# electrosteel2020_10_arrange6_synthboards.net
KiCad netlist of a schematic drawn in EAGLE
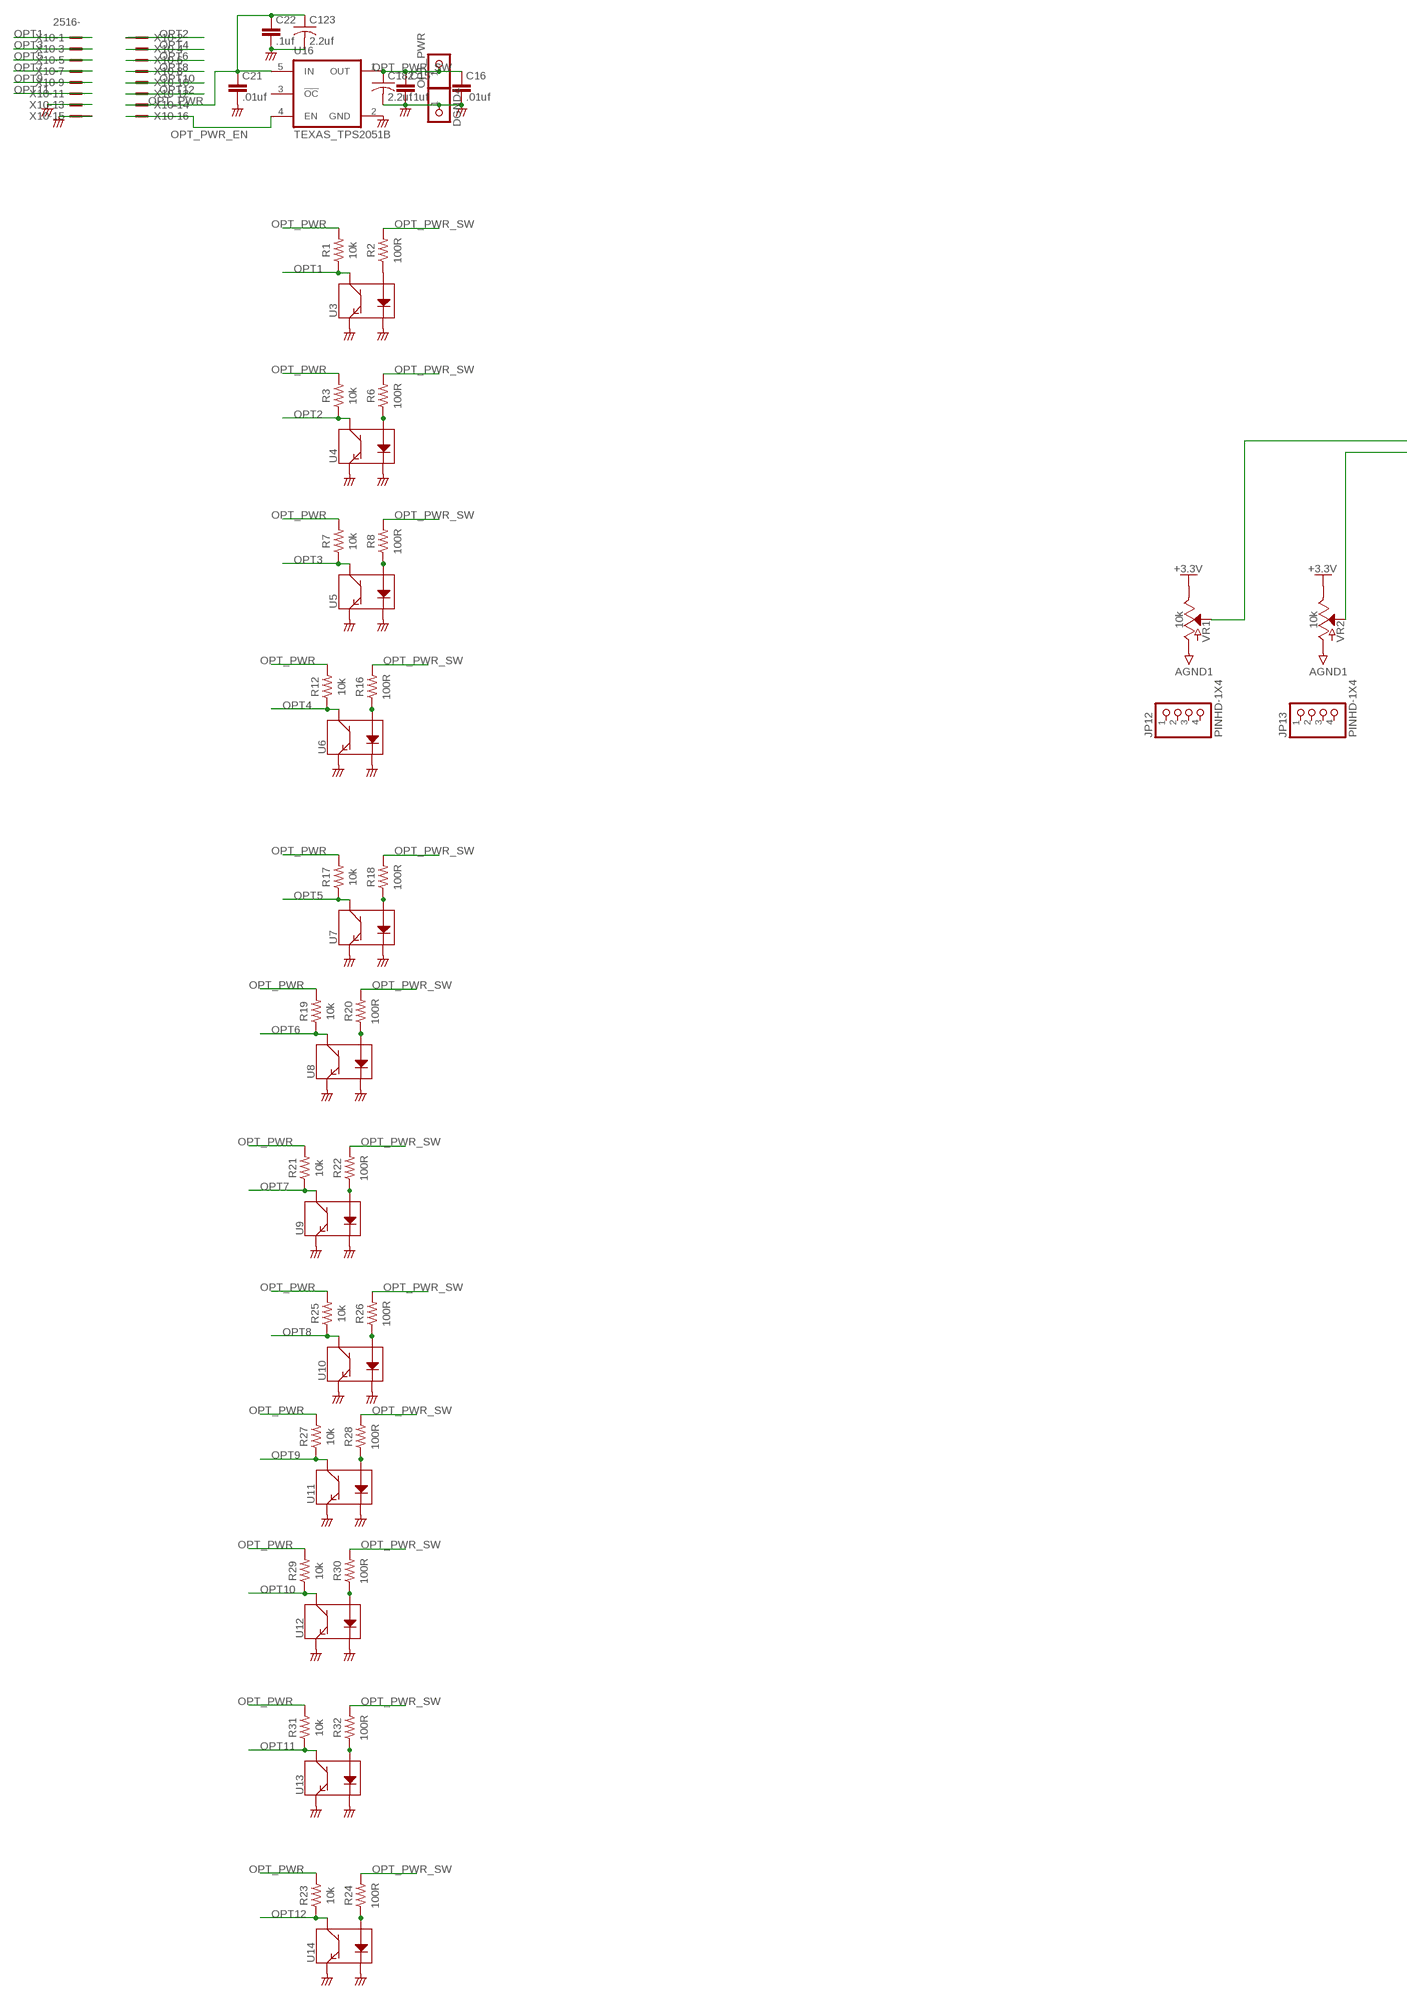
[diagram p0: schematic, sheet 1, part 1 of 3]
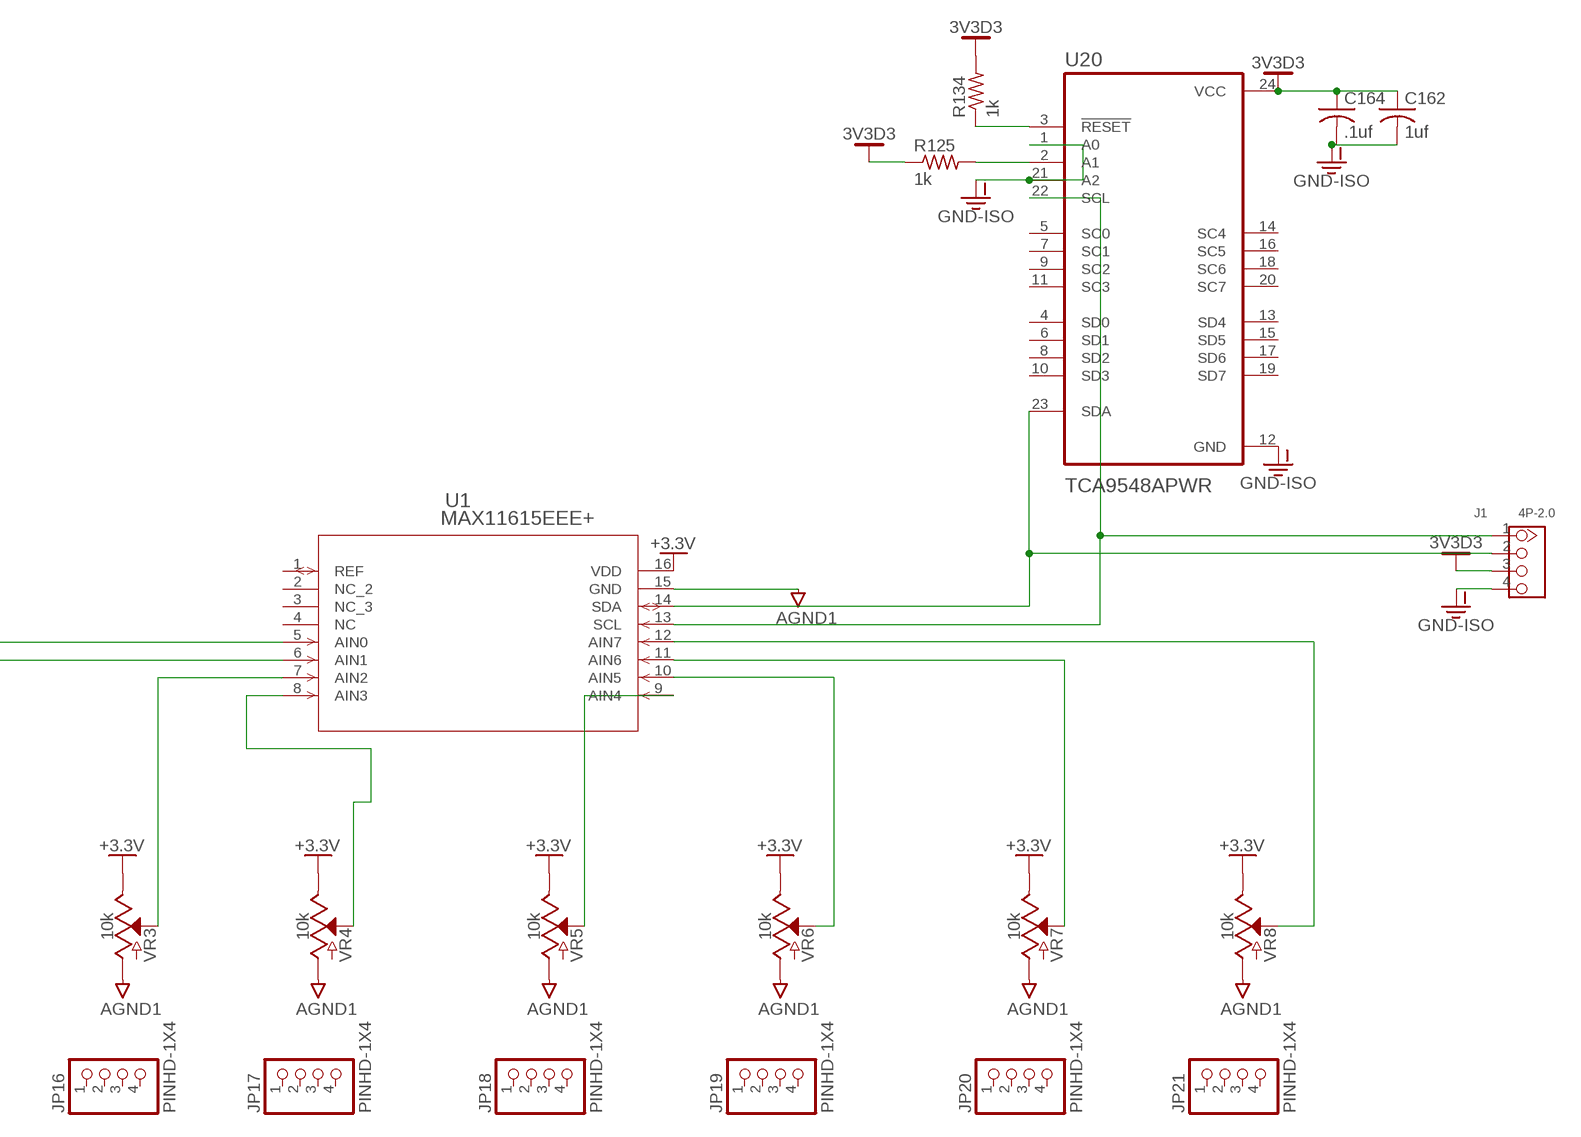
[diagram p1: schematic, sheet 1, part 2 of 3]
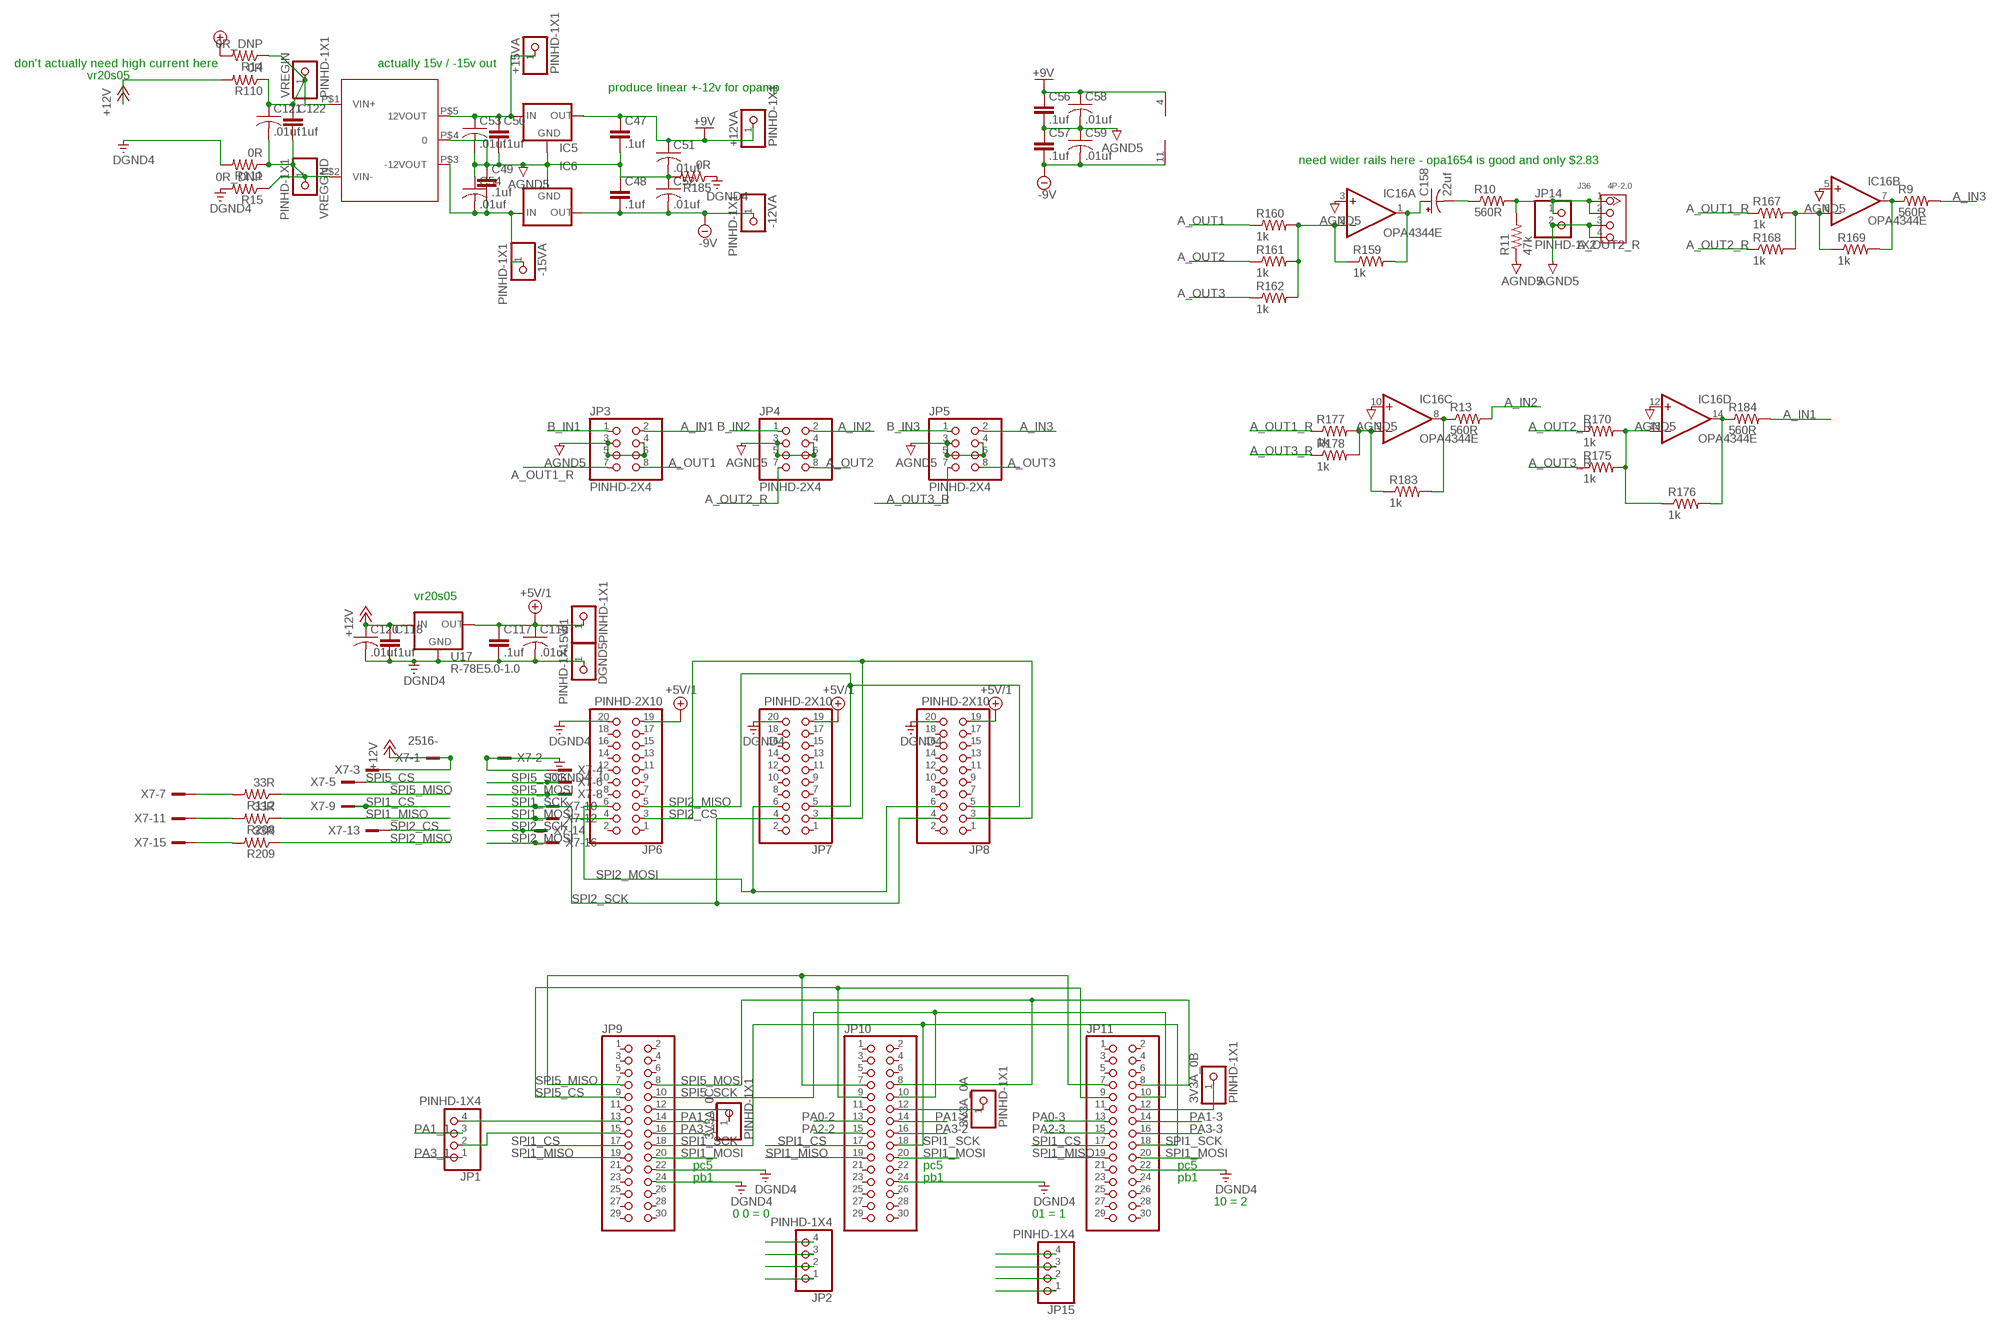
[diagram p2: schematic, sheet 1, part 3 of 3]

(export (version "E")
  (design (tool "Eeschema 10.0.6"))
  (components
    (comp (ref "+12VA")
      (value "PINHD-1X1")
      (footprint "eagle-import:1X01")
      (fields (field (name "PARTNO") "*DNP"))
      (libsource (lib "eagle-import") (part "PINHD-1X1"))
    )
    (comp (ref "+15VA")
      (value "PINHD-1X1")
      (footprint "eagle-import:1X01")
      (fields (field (name "PARTNO") "*DNP"))
      (libsource (lib "eagle-import") (part "PINHD-1X1"))
    )
    (comp (ref "-12VA")
      (value "PINHD-1X1")
      (footprint "eagle-import:1X01")
      (fields (field (name "PARTNO") "*DNP"))
      (libsource (lib "eagle-import") (part "PINHD-1X1"))
    )
    (comp (ref "-15VA")
      (value "PINHD-1X1")
      (footprint "eagle-import:1X01")
      (fields (field (name "PARTNO") "*DNP"))
      (libsource (lib "eagle-import") (part "PINHD-1X1"))
    )
    (comp (ref "3V3A_0A")
      (value "PINHD-1X1")
      (footprint "eagle-import:1X01")
      (fields (field (name "PARTNO") "*DNP"))
      (libsource (lib "eagle-import") (part "PINHD-1X1"))
    )
    (comp (ref "3V3A_0B")
      (value "PINHD-1X1")
      (footprint "eagle-import:1X01")
      (fields (field (name "PARTNO") "*DNP"))
      (libsource (lib "eagle-import") (part "PINHD-1X1"))
    )
    (comp (ref "3V3A_0C")
      (value "PINHD-1X1")
      (footprint "eagle-import:1X01")
      (fields (field (name "PARTNO") "*DNP"))
      (libsource (lib "eagle-import") (part "PINHD-1X1"))
    )
    (comp (ref "5V/1")
      (value "PINHD-1X1")
      (footprint "eagle-import:1X01")
      (fields (field (name "PARTNO") "*DNP"))
      (libsource (lib "eagle-import") (part "PINHD-1X1"))
    )
    (comp (ref "C15")
      (value ".1uf")
      (footprint "eagle-import:0402")
      (fields (field (name "PARTNO") "CC0402KRX7R8BB104"))
      (libsource (lib "eagle-import") (part "CAP_0402"))
    )
    (comp (ref "C16")
      (value ".01uf")
      (footprint "eagle-import:0402")
      (fields (field (name "PARTNO") "CC0402KRX7R8BB103"))
      (libsource (lib "eagle-import") (part "CAP_0402"))
    )
    (comp (ref "C21")
      (value ".01uf")
      (footprint "eagle-import:0402")
      (fields (field (name "PARTNO") "CC0402KRX7R8BB103"))
      (libsource (lib "eagle-import") (part "CAP_0402"))
    )
    (comp (ref "C22")
      (value ".1uf")
      (footprint "eagle-import:0402")
      (fields (field (name "PARTNO") "CC0402KRX7R8BB104"))
      (libsource (lib "eagle-import") (part "CAP_0402"))
    )
    (comp (ref "C47")
      (value ".1uf")
      (footprint "eagle-import:0402")
      (fields (field (name "PARTNO") "CC0402KRX7R8BB104"))
      (libsource (lib "eagle-import") (part "CAP_0402"))
    )
    (comp (ref "C48")
      (value ".1uf")
      (footprint "eagle-import:0402")
      (fields (field (name "PARTNO") "CC0402KRX7R8BB104"))
      (libsource (lib "eagle-import") (part "CAP_0402"))
    )
    (comp (ref "C49")
      (value ".1uf")
      (footprint "eagle-import:0402")
      (fields (field (name "PARTNO") "CC0402KRX7R8BB104"))
      (libsource (lib "eagle-import") (part "CAP_0402"))
    )
    (comp (ref "C50")
      (value ".1uf")
      (footprint "eagle-import:0402")
      (fields (field (name "PARTNO") "CC0402KRX7R8BB104"))
      (libsource (lib "eagle-import") (part "CAP_0402"))
    )
    (comp (ref "C51")
      (value ".01uf")
      (footprint "eagle-import:C0201")
      (fields (field (name "PARTNO") "TMK063B7103KP-F"))
      (libsource (lib "eagle-import") (part "C-USC0201"))
    )
    (comp (ref "C52")
      (value ".01uf")
      (footprint "eagle-import:C0201")
      (fields (field (name "PARTNO") "TMK063B7103KP-F"))
      (libsource (lib "eagle-import") (part "C-USC0201"))
    )
    (comp (ref "C53")
      (value ".01uf")
      (footprint "eagle-import:C0201")
      (fields (field (name "PARTNO") "TMK063B7103KP-F"))
      (libsource (lib "eagle-import") (part "C-USC0201"))
    )
    (comp (ref "C54")
      (value ".01uf")
      (footprint "eagle-import:C0201")
      (fields (field (name "PARTNO") "TMK063B7103KP-F"))
      (libsource (lib "eagle-import") (part "C-USC0201"))
    )
    (comp (ref "C56")
      (value ".1uf")
      (footprint "eagle-import:0402")
      (fields (field (name "PARTNO") "CC0402KRX7R8BB104"))
      (libsource (lib "eagle-import") (part "CAP_0402"))
    )
    (comp (ref "C57")
      (value ".1uf")
      (footprint "eagle-import:0402")
      (fields (field (name "PARTNO") "CC0402KRX7R8BB104"))
      (libsource (lib "eagle-import") (part "CAP_0402"))
    )
    (comp (ref "C58")
      (value ".01uf")
      (footprint "eagle-import:C0201")
      (fields (field (name "PARTNO") "TMK063B7103KP-F"))
      (libsource (lib "eagle-import") (part "C-USC0201"))
    )
    (comp (ref "C59")
      (value ".01uf")
      (footprint "eagle-import:C0201")
      (fields (field (name "PARTNO") "TMK063B7103KP-F"))
      (libsource (lib "eagle-import") (part "C-USC0201"))
    )
    (comp (ref "C117")
      (value ".1uf")
      (footprint "eagle-import:0402")
      (fields (field (name "PARTNO") "CC0402KRX7R8BB104"))
      (libsource (lib "eagle-import") (part "CAP_0402"))
    )
    (comp (ref "C118")
      (value ".1uf")
      (footprint "eagle-import:0402")
      (fields (field (name "PARTNO") "CC0402KRX7R8BB104"))
      (libsource (lib "eagle-import") (part "CAP_0402"))
    )
    (comp (ref "C119")
      (value ".01uf")
      (footprint "eagle-import:C0201")
      (fields (field (name "PARTNO") "TMK063B7103KP-F"))
      (libsource (lib "eagle-import") (part "C-USC0201"))
    )
    (comp (ref "C120")
      (value ".01uf")
      (footprint "eagle-import:C0201")
      (fields (field (name "PARTNO") "TMK063B7103KP-F"))
      (libsource (lib "eagle-import") (part "C-USC0201"))
    )
    (comp (ref "C121")
      (value ".01uf")
      (footprint "eagle-import:C0201")
      (fields (field (name "PARTNO") "TMK063B7103KP-F"))
      (libsource (lib "eagle-import") (part "C-USC0201"))
    )
    (comp (ref "C122")
      (value ".1uf")
      (footprint "eagle-import:0402")
      (fields (field (name "PARTNO") "CC0402KRX7R8BB104"))
      (libsource (lib "eagle-import") (part "CAP_0402"))
    )
    (comp (ref "C123")
      (value "2.2uf")
      (footprint "eagle-import:C1206")
      (fields (field (name "PARTNO") "T491A225K020AT"))
      (libsource (lib "eagle-import") (part "C-USC1206"))
    )
    (comp (ref "C158")
      (value "22uf")
      (footprint "eagle-import:PANASONIC_D")
      (fields (field (name "PARTNO") "EEE-1CA220NP"))
      (libsource (lib "eagle-import") (part "CPOL-USD"))
    )
    (comp (ref "C162")
      (value "1uf")
      (footprint "eagle-import:C1206K")
      (fields (field (name "PARTNO") "C3216X7R1E105K085AA"))
      (libsource (lib "eagle-import") (part "C-USC1206K"))
    )
    (comp (ref "C164")
      (value ".1uf")
      (footprint "eagle-import:C0603K")
      (fields (field (name "PARTNO") "CC0603KRX7R8BB104"))
      (libsource (lib "eagle-import") (part "C-USC0603K"))
    )
    (comp (ref "C182")
      (value "2.2uf")
      (footprint "eagle-import:C1206")
      (fields (field (name "PARTNO") "T491A225K020AT"))
      (libsource (lib "eagle-import") (part "C-USC1206"))
    )
    (comp (ref "DGND4")
      (value "PINHD-1X1")
      (footprint "eagle-import:1X01")
      (fields (field (name "PARTNO") "*DNP"))
      (libsource (lib "eagle-import") (part "adafruit_PINHD-1X1"))
    )
    (comp (ref "DGND5")
      (value "PINHD-1X1")
      (footprint "eagle-import:1X01")
      (fields (field (name "PARTNO") "*DNP"))
      (libsource (lib "eagle-import") (part "PINHD-1X1"))
    )
    (comp (ref "IC5")
      (value "78LXX")
      (footprint "eagle-import:78LXX")
      (fields (field (name "PARTNO") "LM78L12ACZ/LFT7"))
      (libsource (lib "eagle-import") (part "78LXX"))
    )
    (comp (ref "IC6")
      (value "79LXX")
      (footprint "eagle-import:79LXX")
      (fields (field (name "PARTNO") "L79L12ACZ-TR"))
      (libsource (lib "eagle-import") (part "79LXX"))
    )
    (comp (ref "IC16")
      (value "OPA4344E")
      (footprint "eagle-import:TSSOP14")
      (fields (field (name "PARTNO") "OPA1654AIPWR"))
      (libsource (lib "eagle-import") (part "OPA4E344"))
    )
    (comp (ref "J1")
      (value "4P-2.0")
      (footprint "eagle-import:HW4-2.0")
      (fields (field (name "PARTNO") "110990030"))
      (libsource (lib "eagle-import") (part "GROVE-CONNECTOR-DIP(4P-2.0)"))
    )
    (comp (ref "J36")
      (value "4P-2.0")
      (footprint "eagle-import:HW4-2.0")
      (fields (field (name "PARTNO") "110990030"))
      (libsource (lib "eagle-import") (part "GROVE-CONNECTOR-DIP(4P-2.0)"))
    )
    (comp (ref "JP1")
      (value "PINHD-1X4")
      (footprint "eagle-import:1X04")
      (libsource (lib "eagle-import") (part "PINHD-1X4"))
    )
    (comp (ref "JP2")
      (value "PINHD-1X4")
      (footprint "eagle-import:1X04")
      (libsource (lib "eagle-import") (part "PINHD-1X4"))
    )
    (comp (ref "JP3")
      (value "PINHD-2X4")
      (footprint "eagle-import:2X04")
      (fields (field (name "PARTNO") "77313-101-08LF"))
      (libsource (lib "eagle-import") (part "PINHD-2X4"))
    )
    (comp (ref "JP4")
      (value "PINHD-2X4")
      (footprint "eagle-import:2X04")
      (fields (field (name "PARTNO") "77313-101-08LF"))
      (libsource (lib "eagle-import") (part "PINHD-2X4"))
    )
    (comp (ref "JP5")
      (value "PINHD-2X4")
      (footprint "eagle-import:2X04")
      (fields (field (name "PARTNO") "77313-101-08LF"))
      (libsource (lib "eagle-import") (part "PINHD-2X4"))
    )
    (comp (ref "JP6")
      (value "PINHD-2X10")
      (footprint "eagle-import:2X10")
      (fields (field (name "PARTNO") "77313-101-20LF"))
      (libsource (lib "eagle-import") (part "PINHD-2X10"))
    )
    (comp (ref "JP7")
      (value "PINHD-2X10")
      (footprint "eagle-import:2X10")
      (fields (field (name "PARTNO") "77313-101-20LF"))
      (libsource (lib "eagle-import") (part "PINHD-2X10"))
    )
    (comp (ref "JP8")
      (value "PINHD-2X10")
      (footprint "eagle-import:2X10")
      (fields (field (name "PARTNO") "77313-101-20LF"))
      (libsource (lib "eagle-import") (part "PINHD-2X10"))
    )
    (comp (ref "JP9")
      (value "PINHD-2X15")
      (footprint "eagle-import:2X15")
      (fields (field (name "PARTNO") "77313-101-30LF"))
      (libsource (lib "eagle-import") (part "PINHD-2X15"))
    )
    (comp (ref "JP10")
      (value "PINHD-2X15")
      (footprint "eagle-import:2X15")
      (fields (field (name "PARTNO") "77313-101-30LF"))
      (libsource (lib "eagle-import") (part "PINHD-2X15"))
    )
    (comp (ref "JP11")
      (value "PINHD-2X15")
      (footprint "eagle-import:2X15")
      (fields (field (name "PARTNO") "77313-101-30LF"))
      (libsource (lib "eagle-import") (part "PINHD-2X15"))
    )
    (comp (ref "JP12")
      (value "PINHD-1X4")
      (footprint "eagle-import:1X04")
      (libsource (lib "eagle-import") (part "PINHD-1X4"))
    )
    (comp (ref "JP13")
      (value "PINHD-1X4")
      (footprint "eagle-import:1X04")
      (libsource (lib "eagle-import") (part "PINHD-1X4"))
    )
    (comp (ref "JP14")
      (value "PINHD-1X2")
      (footprint "eagle-import:1X02")
      (fields (field (name "PARTNO") "*DNP"))
      (libsource (lib "eagle-import") (part "PINHD-1X2"))
    )
    (comp (ref "JP15")
      (value "PINHD-1X4")
      (footprint "eagle-import:1X04")
      (libsource (lib "eagle-import") (part "PINHD-1X4"))
    )
    (comp (ref "JP16")
      (value "PINHD-1X4")
      (footprint "eagle-import:1X04")
      (libsource (lib "eagle-import") (part "PINHD-1X4"))
    )
    (comp (ref "JP17")
      (value "PINHD-1X4")
      (footprint "eagle-import:1X04")
      (libsource (lib "eagle-import") (part "PINHD-1X4"))
    )
    (comp (ref "JP18")
      (value "PINHD-1X4")
      (footprint "eagle-import:1X04")
      (libsource (lib "eagle-import") (part "PINHD-1X4"))
    )
    (comp (ref "JP19")
      (value "PINHD-1X4")
      (footprint "eagle-import:1X04")
      (libsource (lib "eagle-import") (part "PINHD-1X4"))
    )
    (comp (ref "JP20")
      (value "PINHD-1X4")
      (footprint "eagle-import:1X04")
      (libsource (lib "eagle-import") (part "PINHD-1X4"))
    )
    (comp (ref "JP21")
      (value "PINHD-1X4")
      (footprint "eagle-import:1X04")
      (libsource (lib "eagle-import") (part "PINHD-1X4"))
    )
    (comp (ref "OPT_PWR")
      (value "PINHD-1X1")
      (footprint "eagle-import:1X01")
      (fields (field (name "PARTNO") "*DNP"))
      (libsource (lib "eagle-import") (part "adafruit_PINHD-1X1"))
    )
    (comp (ref "R1")
      (value "10k")
      (footprint "eagle-import:RESC1608X60")
      (fields (field (name "PARTNO") "ESR03EZPF1002"))
      (libsource (lib "eagle-import") (part "R-USCHIP-0603(1608-METRIC)_"))
    )
    (comp (ref "R2")
      (value "100R")
      (footprint "eagle-import:RESC1608X60")
      (fields (field (name "PARTNO") "ESR03EZPJ101"))
      (libsource (lib "eagle-import") (part "R-USCHIP-0603(1608-METRIC)_"))
    )
    (comp (ref "R3")
      (value "10k")
      (footprint "eagle-import:RESC1608X60")
      (fields (field (name "PARTNO") "ESR03EZPF1002"))
      (libsource (lib "eagle-import") (part "R-USCHIP-0603(1608-METRIC)_"))
    )
    (comp (ref "R6")
      (value "100R")
      (footprint "eagle-import:RESC1608X60")
      (fields (field (name "PARTNO") "ESR03EZPJ101"))
      (libsource (lib "eagle-import") (part "R-USCHIP-0603(1608-METRIC)_"))
    )
    (comp (ref "R7")
      (value "10k")
      (footprint "eagle-import:RESC1608X60")
      (fields (field (name "PARTNO") "ESR03EZPF1002"))
      (libsource (lib "eagle-import") (part "R-USCHIP-0603(1608-METRIC)_"))
    )
    (comp (ref "R8")
      (value "100R")
      (footprint "eagle-import:RESC1608X60")
      (fields (field (name "PARTNO") "ESR03EZPJ101"))
      (libsource (lib "eagle-import") (part "R-USCHIP-0603(1608-METRIC)_"))
    )
    (comp (ref "R9")
      (value "560R")
      (footprint "eagle-import:R0603")
      (fields (field (name "PARTNO") "ESR03EZPF5600"))
      (libsource (lib "eagle-import") (part "R-US_R0603"))
    )
    (comp (ref "R10")
      (value "560R")
      (footprint "eagle-import:R0603")
      (fields (field (name "PARTNO") "ESR03EZPF5600"))
      (libsource (lib "eagle-import") (part "R-US_R0603"))
    )
    (comp (ref "R11")
      (value "47k")
      (footprint "eagle-import:R0603")
      (fields (field (name "PARTNO") "ESR03EZPJ473"))
      (libsource (lib "eagle-import") (part "R-US_R0603"))
    )
    (comp (ref "R12")
      (value "10k")
      (footprint "eagle-import:RESC1608X60")
      (fields (field (name "PARTNO") "ESR03EZPF1002"))
      (libsource (lib "eagle-import") (part "R-USCHIP-0603(1608-METRIC)_"))
    )
    (comp (ref "R13")
      (value "560R")
      (footprint "eagle-import:R0603")
      (fields (field (name "PARTNO") "ESR03EZPF5600"))
      (libsource (lib "eagle-import") (part "R-US_R0603"))
    )
    (comp (ref "R14")
      (value "0R_DNP")
      (footprint "eagle-import:R0603")
      (fields (field (name "PARTNO") "*DNP"))
      (libsource (lib "eagle-import") (part "R-US_R0603"))
    )
    (comp (ref "R15")
      (value "0R_DNP")
      (footprint "eagle-import:R0603")
      (fields (field (name "PARTNO") "*DNP"))
      (libsource (lib "eagle-import") (part "R-US_R0603"))
    )
    (comp (ref "R16")
      (value "100R")
      (footprint "eagle-import:RESC1608X60")
      (fields (field (name "PARTNO") "ESR03EZPJ101"))
      (libsource (lib "eagle-import") (part "R-USCHIP-0603(1608-METRIC)_"))
    )
    (comp (ref "R17")
      (value "10k")
      (footprint "eagle-import:RESC1608X60")
      (fields (field (name "PARTNO") "ESR03EZPF1002"))
      (libsource (lib "eagle-import") (part "R-USCHIP-0603(1608-METRIC)_"))
    )
    (comp (ref "R18")
      (value "100R")
      (footprint "eagle-import:RESC1608X60")
      (fields (field (name "PARTNO") "ESR03EZPJ101"))
      (libsource (lib "eagle-import") (part "R-USCHIP-0603(1608-METRIC)_"))
    )
    (comp (ref "R19")
      (value "10k")
      (footprint "eagle-import:RESC1608X60")
      (fields (field (name "PARTNO") "ESR03EZPF1002"))
      (libsource (lib "eagle-import") (part "R-USCHIP-0603(1608-METRIC)_"))
    )
    (comp (ref "R20")
      (value "100R")
      (footprint "eagle-import:RESC1608X60")
      (fields (field (name "PARTNO") "ESR03EZPJ101"))
      (libsource (lib "eagle-import") (part "R-USCHIP-0603(1608-METRIC)_"))
    )
    (comp (ref "R21")
      (value "10k")
      (footprint "eagle-import:RESC1608X60")
      (fields (field (name "PARTNO") "ESR03EZPF1002"))
      (libsource (lib "eagle-import") (part "R-USCHIP-0603(1608-METRIC)_"))
    )
    (comp (ref "R22")
      (value "100R")
      (footprint "eagle-import:RESC1608X60")
      (fields (field (name "PARTNO") "ESR03EZPJ101"))
      (libsource (lib "eagle-import") (part "R-USCHIP-0603(1608-METRIC)_"))
    )
    (comp (ref "R23")
      (value "10k")
      (footprint "eagle-import:RESC1608X60")
      (fields (field (name "PARTNO") "ESR03EZPF1002"))
      (libsource (lib "eagle-import") (part "R-USCHIP-0603(1608-METRIC)_"))
    )
    (comp (ref "R24")
      (value "100R")
      (footprint "eagle-import:RESC1608X60")
      (fields (field (name "PARTNO") "ESR03EZPJ101"))
      (libsource (lib "eagle-import") (part "R-USCHIP-0603(1608-METRIC)_"))
    )
    (comp (ref "R25")
      (value "10k")
      (footprint "eagle-import:RESC1608X60")
      (fields (field (name "PARTNO") "ESR03EZPF1002"))
      (libsource (lib "eagle-import") (part "R-USCHIP-0603(1608-METRIC)_"))
    )
    (comp (ref "R26")
      (value "100R")
      (footprint "eagle-import:RESC1608X60")
      (fields (field (name "PARTNO") "ESR03EZPJ101"))
      (libsource (lib "eagle-import") (part "R-USCHIP-0603(1608-METRIC)_"))
    )
    (comp (ref "R27")
      (value "10k")
      (footprint "eagle-import:RESC1608X60")
      (fields (field (name "PARTNO") "ESR03EZPF1002"))
      (libsource (lib "eagle-import") (part "R-USCHIP-0603(1608-METRIC)_"))
    )
    (comp (ref "R28")
      (value "100R")
      (footprint "eagle-import:RESC1608X60")
      (fields (field (name "PARTNO") "ESR03EZPJ101"))
      (libsource (lib "eagle-import") (part "R-USCHIP-0603(1608-METRIC)_"))
    )
    (comp (ref "R29")
      (value "10k")
      (footprint "eagle-import:RESC1608X60")
      (fields (field (name "PARTNO") "ESR03EZPF1002"))
      (libsource (lib "eagle-import") (part "R-USCHIP-0603(1608-METRIC)_"))
    )
    (comp (ref "R30")
      (value "100R")
      (footprint "eagle-import:RESC1608X60")
      (fields (field (name "PARTNO") "ESR03EZPJ101"))
      (libsource (lib "eagle-import") (part "R-USCHIP-0603(1608-METRIC)_"))
    )
    (comp (ref "R31")
      (value "10k")
      (footprint "eagle-import:RESC1608X60")
      (fields (field (name "PARTNO") "ESR03EZPF1002"))
      (libsource (lib "eagle-import") (part "R-USCHIP-0603(1608-METRIC)_"))
    )
    (comp (ref "R32")
      (value "100R")
      (footprint "eagle-import:RESC1608X60")
      (fields (field (name "PARTNO") "ESR03EZPJ101"))
      (libsource (lib "eagle-import") (part "R-USCHIP-0603(1608-METRIC)_"))
    )
    (comp (ref "R110")
      (value "0R")
      (footprint "eagle-import:R0603")
      (fields (field (name "PARTNO") "RCS06030000Z0EA"))
      (libsource (lib "eagle-import") (part "R-US_R0603"))
    )
    (comp (ref "R111")
      (value "0R")
      (footprint "eagle-import:R0603")
      (fields (field (name "PARTNO") "RCS06030000Z0EA"))
      (libsource (lib "eagle-import") (part "R-US_R0603"))
    )
    (comp (ref "R112")
      (value "33R")
      (footprint "eagle-import:R0201")
      (fields (field (name "PARTNO") "RC0201FR-0733RL"))
      (libsource (lib "eagle-import") (part "R-US_R0201"))
    )
    (comp (ref "R125")
      (value "1k")
      (footprint "eagle-import:R0603")
      (fields (field (name "PARTNO") "ESR03EZPF1001"))
      (libsource (lib "eagle-import") (part "R-US_R0603"))
    )
    (comp (ref "R134")
      (value "1k")
      (footprint "eagle-import:R0603")
      (fields (field (name "PARTNO") "ESR03EZPF1001"))
      (libsource (lib "eagle-import") (part "R-US_R0603"))
    )
    (comp (ref "R159")
      (value "1k")
      (footprint "eagle-import:R0603")
      (fields (field (name "PARTNO") "ESR03EZPF1001"))
      (libsource (lib "eagle-import") (part "R-US_R0603"))
    )
    (comp (ref "R160")
      (value "1k")
      (footprint "eagle-import:R0603")
      (fields (field (name "PARTNO") "ESR03EZPF1001"))
      (libsource (lib "eagle-import") (part "R-US_R0603"))
    )
    (comp (ref "R161")
      (value "1k")
      (footprint "eagle-import:R0603")
      (fields (field (name "PARTNO") "ESR03EZPF1001"))
      (libsource (lib "eagle-import") (part "R-US_R0603"))
    )
    (comp (ref "R162")
      (value "1k")
      (footprint "eagle-import:R0603")
      (fields (field (name "PARTNO") "ESR03EZPF1001"))
      (libsource (lib "eagle-import") (part "R-US_R0603"))
    )
    (comp (ref "R167")
      (value "1k")
      (footprint "eagle-import:R0603")
      (fields (field (name "PARTNO") "ESR03EZPF1001"))
      (libsource (lib "eagle-import") (part "R-US_R0603"))
    )
    (comp (ref "R168")
      (value "1k")
      (footprint "eagle-import:R0603")
      (fields (field (name "PARTNO") "ESR03EZPF1001"))
      (libsource (lib "eagle-import") (part "R-US_R0603"))
    )
    (comp (ref "R169")
      (value "1k")
      (footprint "eagle-import:R0603")
      (fields (field (name "PARTNO") "ESR03EZPF1001"))
      (libsource (lib "eagle-import") (part "R-US_R0603"))
    )
    (comp (ref "R170")
      (value "1k")
      (footprint "eagle-import:R0603")
      (fields (field (name "PARTNO") "ESR03EZPF1001"))
      (libsource (lib "eagle-import") (part "R-US_R0603"))
    )
    (comp (ref "R175")
      (value "1k")
      (footprint "eagle-import:R0603")
      (fields (field (name "PARTNO") "ESR03EZPF1001"))
      (libsource (lib "eagle-import") (part "R-US_R0603"))
    )
    (comp (ref "R176")
      (value "1k")
      (footprint "eagle-import:R0603")
      (fields (field (name "PARTNO") "ESR03EZPF1001"))
      (libsource (lib "eagle-import") (part "R-US_R0603"))
    )
    (comp (ref "R177")
      (value "1k")
      (footprint "eagle-import:R0603")
      (fields (field (name "PARTNO") "ESR03EZPF1001"))
      (libsource (lib "eagle-import") (part "R-US_R0603"))
    )
    (comp (ref "R178")
      (value "1k")
      (footprint "eagle-import:R0603")
      (fields (field (name "PARTNO") "ESR03EZPF1001"))
      (libsource (lib "eagle-import") (part "R-US_R0603"))
    )
    (comp (ref "R183")
      (value "1k")
      (footprint "eagle-import:R0603")
      (fields (field (name "PARTNO") "ESR03EZPF1001"))
      (libsource (lib "eagle-import") (part "R-US_R0603"))
    )
    (comp (ref "R184")
      (value "560R")
      (footprint "eagle-import:R0603")
      (fields (field (name "PARTNO") "ESR03EZPF5600"))
      (libsource (lib "eagle-import") (part "R-US_R0603"))
    )
    (comp (ref "R185")
      (value "0R")
      (footprint "eagle-import:R0603")
      (fields (field (name "PARTNO") "RCS06030000Z0EA"))
      (libsource (lib "eagle-import") (part "R-US_R0603"))
    )
    (comp (ref "R208")
      (value "33R")
      (footprint "eagle-import:R0201")
      (fields (field (name "PARTNO") "RC0201FR-0733RL"))
      (libsource (lib "eagle-import") (part "R-US_R0201"))
    )
    (comp (ref "R209")
      (value "33R")
      (footprint "eagle-import:R0201")
      (fields (field (name "PARTNO") "RC0201FR-0733RL"))
      (libsource (lib "eagle-import") (part "R-US_R0201"))
    )
    (comp (ref "U$3")
      (value "CMR0512S3C")
      (footprint "eagle-import:CMR0512S3C")
      (fields (field (name "PARTNO") "DPU01M-15"))
      (libsource (lib "eagle-import") (part "CMR0512S3C"))
    )
    (comp (ref "U1")
      (value "MAX11615EEE+")
      (footprint "eagle-import:21-0055H_16_MXM")
      (fields (field (name "MANUFACTURER_PART_NUMBER") "max11615eee+"))
      (libsource (lib "eagle-import") (part "MAX11615EEE+"))
    )
    (comp (ref "U3")
      (value "QRE1113")
      (footprint "eagle-import:QRE1113")
      (fields (field (name "PARTNO") "QRE1113GR"))
      (libsource (lib "eagle-import") (part "QRE1113"))
    )
    (comp (ref "U4")
      (value "QRE1113")
      (footprint "eagle-import:QRE1113")
      (fields (field (name "PARTNO") "QRE1113GR"))
      (libsource (lib "eagle-import") (part "QRE1113"))
    )
    (comp (ref "U5")
      (value "QRE1113")
      (footprint "eagle-import:QRE1113")
      (fields (field (name "PARTNO") "QRE1113GR"))
      (libsource (lib "eagle-import") (part "QRE1113"))
    )
    (comp (ref "U6")
      (value "QRE1113")
      (footprint "eagle-import:QRE1113")
      (fields (field (name "PARTNO") "QRE1113GR"))
      (libsource (lib "eagle-import") (part "QRE1113"))
    )
    (comp (ref "U7")
      (value "QRE1113")
      (footprint "eagle-import:QRE1113")
      (fields (field (name "PARTNO") "QRE1113GR"))
      (libsource (lib "eagle-import") (part "QRE1113"))
    )
    (comp (ref "U8")
      (value "QRE1113")
      (footprint "eagle-import:QRE1113")
      (fields (field (name "PARTNO") "QRE1113GR"))
      (libsource (lib "eagle-import") (part "QRE1113"))
    )
    (comp (ref "U9")
      (value "QRE1113")
      (footprint "eagle-import:QRE1113")
      (fields (field (name "PARTNO") "QRE1113GR"))
      (libsource (lib "eagle-import") (part "QRE1113"))
    )
    (comp (ref "U10")
      (value "QRE1113")
      (footprint "eagle-import:QRE1113")
      (fields (field (name "PARTNO") "QRE1113GR"))
      (libsource (lib "eagle-import") (part "QRE1113"))
    )
    (comp (ref "U11")
      (value "QRE1113")
      (footprint "eagle-import:QRE1113")
      (fields (field (name "PARTNO") "QRE1113GR"))
      (libsource (lib "eagle-import") (part "QRE1113"))
    )
    (comp (ref "U12")
      (value "QRE1113")
      (footprint "eagle-import:QRE1113")
      (fields (field (name "PARTNO") "QRE1113GR"))
      (libsource (lib "eagle-import") (part "QRE1113"))
    )
    (comp (ref "U13")
      (value "QRE1113")
      (footprint "eagle-import:QRE1113")
      (fields (field (name "PARTNO") "QRE1113GR"))
      (libsource (lib "eagle-import") (part "QRE1113"))
    )
    (comp (ref "U14")
      (value "QRE1113")
      (footprint "eagle-import:QRE1113")
      (fields (field (name "PARTNO") "QRE1113GR"))
      (libsource (lib "eagle-import") (part "QRE1113"))
    )
    (comp (ref "U16")
      (value "TEXAS_TPS2051B")
      (footprint "eagle-import:TEXAS_SOT23-5")
      (fields (field (name "PARTNO") "TPS2051BDBVRG4"))
      (libsource (lib "eagle-import") (part "TEXAS_TPS2051B"))
    )
    (comp (ref "U17")
      (value "R-78E5.0-1.0")
      (footprint "eagle-import:DC-DC_CONVERTER_78XX")
      (libsource (lib "eagle-import") (part "R-78E5.0-1.0"))
    )
    (comp (ref "U20")
      (value "TCA9548APWR")
      (footprint "eagle-import:SOP65P640X120-24N")
      (fields (field (name "MF") "Texas Instruments"))
      (libsource (lib "eagle-import") (part "TCA9548APWR"))
    )
    (comp (ref "VR1")
      (value "10k")
      (footprint "eagle-import:POT-PTH-ALPS")
      (libsource (lib "eagle-import") (part "POTENTIOMETER-PTH-9MM-1/20W-20%"))
    )
    (comp (ref "VR2")
      (value "10k")
      (footprint "eagle-import:POT-PTH-ALPS")
      (libsource (lib "eagle-import") (part "POTENTIOMETER-PTH-9MM-1/20W-20%"))
    )
    (comp (ref "VR3")
      (value "10k")
      (footprint "eagle-import:POT-PTH-ALPS")
      (libsource (lib "eagle-import") (part "POTENTIOMETER-PTH-9MM-1/20W-20%"))
    )
    (comp (ref "VR4")
      (value "10k")
      (footprint "eagle-import:POT-PTH-ALPS")
      (libsource (lib "eagle-import") (part "POTENTIOMETER-PTH-9MM-1/20W-20%"))
    )
    (comp (ref "VR5")
      (value "10k")
      (footprint "eagle-import:POT-PTH-ALPS")
      (libsource (lib "eagle-import") (part "POTENTIOMETER-PTH-9MM-1/20W-20%"))
    )
    (comp (ref "VR6")
      (value "10k")
      (footprint "eagle-import:POT-PTH-ALPS")
      (libsource (lib "eagle-import") (part "POTENTIOMETER-PTH-9MM-1/20W-20%"))
    )
    (comp (ref "VR7")
      (value "10k")
      (footprint "eagle-import:POT-PTH-ALPS")
      (libsource (lib "eagle-import") (part "POTENTIOMETER-PTH-9MM-1/20W-20%"))
    )
    (comp (ref "VR8")
      (value "10k")
      (footprint "eagle-import:POT-PTH-ALPS")
      (libsource (lib "eagle-import") (part "POTENTIOMETER-PTH-9MM-1/20W-20%"))
    )
    (comp (ref "VREGGND")
      (value "PINHD-1X1")
      (footprint "eagle-import:1X01")
      (fields (field (name "PARTNO") "*DNP"))
      (libsource (lib "eagle-import") (part "PINHD-1X1"))
    )
    (comp (ref "VREGIN")
      (value "PINHD-1X1")
      (footprint "eagle-import:1X01")
      (fields (field (name "PARTNO") "*DNP"))
      (libsource (lib "eagle-import") (part "PINHD-1X1"))
    )
    (comp (ref "X7")
      (value "2516-")
      (footprint "eagle-import:PAK100_2500-16")
      (fields (field (name "PARTNO") "D2516-6002-AR"))
      (libsource (lib "eagle-import") (part "2516-"))
    )
    (comp (ref "X10")
      (value "2516-")
      (footprint "eagle-import:PAK100_2500-16")
      (fields (field (name "PARTNO") "D2516-6002-AR"))
      (libsource (lib "eagle-import") (part "2516-"))
    )
  )
  (nets
    (net (code "1") (name "+3.3V") (class "Default")
      (node (ref "U1") (pin "16") (pinfunction "VDD_16") (pintype "power_in"))
      (node (ref "VR1") (pin "P$1") (pinfunction "E_P$1") (pintype "passive"))
      (node (ref "VR2") (pin "P$1") (pinfunction "E_P$1") (pintype "passive"))
      (node (ref "VR3") (pin "P$1") (pinfunction "E_P$1") (pintype "passive"))
      (node (ref "VR4") (pin "P$1") (pinfunction "E_P$1") (pintype "passive"))
      (node (ref "VR5") (pin "P$1") (pinfunction "E_P$1") (pintype "passive"))
      (node (ref "VR6") (pin "P$1") (pinfunction "E_P$1") (pintype "passive"))
      (node (ref "VR7") (pin "P$1") (pinfunction "E_P$1") (pintype "passive"))
      (node (ref "VR8") (pin "P$1") (pinfunction "E_P$1") (pintype "passive"))
    )
    (net (code "2") (name "+5V{slash}1") (class "Default")
      (node (ref "5V/1") (pin "1") (pinfunction "1_1") (pintype "passive"))
      (node (ref "C117") (pin "1") (pinfunction "1_1") (pintype "passive"))
      (node (ref "C119") (pin "1") (pinfunction "1_1") (pintype "passive"))
      (node (ref "JP6") (pin "19") (pinfunction "19_19") (pintype "passive"))
      (node (ref "JP7") (pin "19") (pinfunction "19_19") (pintype "passive"))
      (node (ref "JP8") (pin "19") (pinfunction "19_19") (pintype "passive"))
      (node (ref "R14") (pin "2") (pinfunction "2_2") (pintype "passive"))
      (node (ref "U17") (pin "VOUT") (pinfunction "OUT_VOUT") (pintype "passive"))
    )
    (net (code "3") (name "+9V") (class "Default")
      (node (ref "+12VA") (pin "1") (pinfunction "1_1") (pintype "passive"))
      (node (ref "C47") (pin "1") (pinfunction "1_1") (pintype "passive"))
      (node (ref "C51") (pin "1") (pinfunction "1_1") (pintype "passive"))
      (node (ref "C56") (pin "1") (pinfunction "1_1") (pintype "passive"))
      (node (ref "C58") (pin "1") (pinfunction "1_1") (pintype "passive"))
      (node (ref "IC16") (pin "4") (pinfunction "V+_4") (pintype "power_in"))
      (node (ref "IC5") (pin "OUT") (pinfunction "OUT_OUT") (pintype "passive"))
    )
    (net (code "4") (name "+12V") (class "Default")
      (node (ref "C118") (pin "1") (pinfunction "1_1") (pintype "passive"))
      (node (ref "C120") (pin "1") (pinfunction "1_1") (pintype "passive"))
      (node (ref "R110") (pin "2") (pinfunction "2_2") (pintype "passive"))
      (node (ref "U17") (pin "VIN") (pinfunction "IN_VIN") (pintype "input"))
      (node (ref "X7") (pin "1") (pinfunction "KL_1") (pintype "passive"))
      (node (ref "X7") (pin "3") (pinfunction "KL_3") (pintype "passive"))
    )
    (net (code "5") (name "-9V") (class "Default")
      (node (ref "-12VA") (pin "1") (pinfunction "1_1") (pintype "passive"))
      (node (ref "C48") (pin "2") (pinfunction "2_2") (pintype "passive"))
      (node (ref "C52") (pin "2") (pinfunction "2_2") (pintype "passive"))
      (node (ref "C57") (pin "2") (pinfunction "2_2") (pintype "passive"))
      (node (ref "C59") (pin "2") (pinfunction "2_2") (pintype "passive"))
      (node (ref "IC16") (pin "11") (pinfunction "V-_11") (pintype "power_in"))
      (node (ref "IC6") (pin "OUT") (pinfunction "OUT_OUT") (pintype "passive"))
    )
    (net (code "6") (name "/A_IN1") (class "Default")
      (node (ref "JP3") (pin "2") (pinfunction "2_2") (pintype "passive"))
      (node (ref "R184") (pin "2") (pinfunction "2_2") (pintype "passive"))
    )
    (net (code "7") (name "/A_IN2") (class "Default")
      (node (ref "JP4") (pin "2") (pinfunction "2_2") (pintype "passive"))
      (node (ref "R13") (pin "2") (pinfunction "2_2") (pintype "passive"))
    )
    (net (code "8") (name "/A_IN3") (class "Default")
      (node (ref "JP5") (pin "2") (pinfunction "2_2") (pintype "passive"))
      (node (ref "R9") (pin "2") (pinfunction "2_2") (pintype "passive"))
    )
    (net (code "9") (name "/A_OUT1") (class "Default")
      (node (ref "JP3") (pin "8") (pinfunction "8_8") (pintype "passive"))
      (node (ref "R160") (pin "1") (pinfunction "1_1") (pintype "passive"))
    )
    (net (code "10") (name "/A_OUT1_R") (class "Default")
      (node (ref "JP3") (pin "7") (pinfunction "7_7") (pintype "passive"))
      (node (ref "R167") (pin "1") (pinfunction "1_1") (pintype "passive"))
      (node (ref "R177") (pin "1") (pinfunction "1_1") (pintype "passive"))
    )
    (net (code "11") (name "/A_OUT2") (class "Default")
      (node (ref "JP4") (pin "8") (pinfunction "8_8") (pintype "passive"))
      (node (ref "R161") (pin "1") (pinfunction "1_1") (pintype "passive"))
    )
    (net (code "12") (name "/A_OUT2_R") (class "Default")
      (node (ref "JP4") (pin "7") (pinfunction "7_7") (pintype "passive"))
      (node (ref "R168") (pin "1") (pinfunction "1_1") (pintype "passive"))
      (node (ref "R170") (pin "1") (pinfunction "1_1") (pintype "passive"))
    )
    (net (code "13") (name "/A_OUT3") (class "Default")
      (node (ref "JP5") (pin "8") (pinfunction "8_8") (pintype "passive"))
      (node (ref "R162") (pin "1") (pinfunction "1_1") (pintype "passive"))
    )
    (net (code "14") (name "/A_OUT3_R") (class "Default")
      (node (ref "JP5") (pin "7") (pinfunction "7_7") (pintype "passive"))
      (node (ref "R175") (pin "1") (pinfunction "1_1") (pintype "passive"))
      (node (ref "R178") (pin "1") (pinfunction "1_1") (pintype "passive"))
    )
    (net (code "15") (name "/B_IN1") (class "Default")
      (node (ref "JP3") (pin "1") (pinfunction "1_1") (pintype "passive"))
    )
    (net (code "16") (name "/B_IN2") (class "Default")
      (node (ref "JP4") (pin "1") (pinfunction "1_1") (pintype "passive"))
    )
    (net (code "17") (name "/B_IN3") (class "Default")
      (node (ref "JP5") (pin "1") (pinfunction "1_1") (pintype "passive"))
    )
    (net (code "18") (name "/OPT1") (class "Default")
      (node (ref "R1") (pin "1") (pinfunction "1_1") (pintype "passive"))
      (node (ref "U3") (pin "3") (pinfunction "C_3") (pintype "bidirectional"))
      (node (ref "X10") (pin "1") (pinfunction "KL_1") (pintype "passive"))
    )
    (net (code "19") (name "/OPT2") (class "Default")
      (node (ref "R3") (pin "1") (pinfunction "1_1") (pintype "passive"))
      (node (ref "U4") (pin "3") (pinfunction "C_3") (pintype "bidirectional"))
      (node (ref "X10") (pin "2") (pinfunction "KL_2") (pintype "passive"))
    )
    (net (code "20") (name "/OPT3") (class "Default")
      (node (ref "R7") (pin "1") (pinfunction "1_1") (pintype "passive"))
      (node (ref "U5") (pin "3") (pinfunction "C_3") (pintype "bidirectional"))
      (node (ref "X10") (pin "3") (pinfunction "KL_3") (pintype "passive"))
    )
    (net (code "21") (name "/OPT4") (class "Default")
      (node (ref "R12") (pin "1") (pinfunction "1_1") (pintype "passive"))
      (node (ref "U6") (pin "3") (pinfunction "C_3") (pintype "bidirectional"))
      (node (ref "X10") (pin "4") (pinfunction "KL_4") (pintype "passive"))
    )
    (net (code "22") (name "/OPT5") (class "Default")
      (node (ref "R17") (pin "1") (pinfunction "1_1") (pintype "passive"))
      (node (ref "U7") (pin "3") (pinfunction "C_3") (pintype "bidirectional"))
      (node (ref "X10") (pin "5") (pinfunction "KL_5") (pintype "passive"))
    )
    (net (code "23") (name "/OPT6") (class "Default")
      (node (ref "R19") (pin "1") (pinfunction "1_1") (pintype "passive"))
      (node (ref "U8") (pin "3") (pinfunction "C_3") (pintype "bidirectional"))
      (node (ref "X10") (pin "6") (pinfunction "KL_6") (pintype "passive"))
    )
    (net (code "24") (name "/OPT7") (class "Default")
      (node (ref "R21") (pin "1") (pinfunction "1_1") (pintype "passive"))
      (node (ref "U9") (pin "3") (pinfunction "C_3") (pintype "bidirectional"))
      (node (ref "X10") (pin "7") (pinfunction "KL_7") (pintype "passive"))
    )
    (net (code "25") (name "/OPT8") (class "Default")
      (node (ref "R25") (pin "1") (pinfunction "1_1") (pintype "passive"))
      (node (ref "U10") (pin "3") (pinfunction "C_3") (pintype "bidirectional"))
      (node (ref "X10") (pin "8") (pinfunction "KL_8") (pintype "passive"))
    )
    (net (code "26") (name "/OPT9") (class "Default")
      (node (ref "R27") (pin "1") (pinfunction "1_1") (pintype "passive"))
      (node (ref "U11") (pin "3") (pinfunction "C_3") (pintype "bidirectional"))
      (node (ref "X10") (pin "9") (pinfunction "KL_9") (pintype "passive"))
    )
    (net (code "27") (name "/OPT10") (class "Default")
      (node (ref "R29") (pin "1") (pinfunction "1_1") (pintype "passive"))
      (node (ref "U12") (pin "3") (pinfunction "C_3") (pintype "bidirectional"))
      (node (ref "X10") (pin "10") (pinfunction "KL_10") (pintype "passive"))
    )
    (net (code "28") (name "/OPT11") (class "Default")
      (node (ref "R31") (pin "1") (pinfunction "1_1") (pintype "passive"))
      (node (ref "U13") (pin "3") (pinfunction "C_3") (pintype "bidirectional"))
      (node (ref "X10") (pin "11") (pinfunction "KL_11") (pintype "passive"))
    )
    (net (code "29") (name "/OPT12") (class "Default")
      (node (ref "R23") (pin "1") (pinfunction "1_1") (pintype "passive"))
      (node (ref "U14") (pin "3") (pinfunction "C_3") (pintype "bidirectional"))
      (node (ref "X10") (pin "12") (pinfunction "KL_12") (pintype "passive"))
    )
    (net (code "30") (name "/OPT_PWR") (class "Default")
      (node (ref "C123") (pin "1") (pinfunction "1_1") (pintype "passive"))
      (node (ref "C21") (pin "1") (pinfunction "1_1") (pintype "passive"))
      (node (ref "C22") (pin "1") (pinfunction "1_1") (pintype "passive"))
      (node (ref "R1") (pin "2") (pinfunction "2_2") (pintype "passive"))
      (node (ref "R12") (pin "2") (pinfunction "2_2") (pintype "passive"))
      (node (ref "R17") (pin "2") (pinfunction "2_2") (pintype "passive"))
      (node (ref "R19") (pin "2") (pinfunction "2_2") (pintype "passive"))
      (node (ref "R21") (pin "2") (pinfunction "2_2") (pintype "passive"))
      (node (ref "R23") (pin "2") (pinfunction "2_2") (pintype "passive"))
      (node (ref "R25") (pin "2") (pinfunction "2_2") (pintype "passive"))
      (node (ref "R27") (pin "2") (pinfunction "2_2") (pintype "passive"))
      (node (ref "R29") (pin "2") (pinfunction "2_2") (pintype "passive"))
      (node (ref "R3") (pin "2") (pinfunction "2_2") (pintype "passive"))
      (node (ref "R31") (pin "2") (pinfunction "2_2") (pintype "passive"))
      (node (ref "R7") (pin "2") (pinfunction "2_2") (pintype "passive"))
      (node (ref "U16") (pin "5") (pinfunction "IN_5") (pintype "input"))
      (node (ref "X10") (pin "14") (pinfunction "KL_14") (pintype "passive"))
    )
    (net (code "31") (name "/OPT_PWR_EN") (class "Default")
      (node (ref "U16") (pin "4") (pinfunction "EN_4") (pintype "input"))
      (node (ref "X10") (pin "16") (pinfunction "KL_16") (pintype "passive"))
    )
    (net (code "32") (name "/OPT_PWR_SW") (class "Default")
      (node (ref "C15") (pin "1") (pinfunction "1_1") (pintype "passive"))
      (node (ref "C16") (pin "1") (pinfunction "1_1") (pintype "passive"))
      (node (ref "C182") (pin "1") (pinfunction "1_1") (pintype "passive"))
      (node (ref "OPT_PWR") (pin "1") (pinfunction "1_1") (pintype "passive"))
      (node (ref "R16") (pin "2") (pinfunction "2_2") (pintype "passive"))
      (node (ref "R18") (pin "2") (pinfunction "2_2") (pintype "passive"))
      (node (ref "R2") (pin "2") (pinfunction "2_2") (pintype "passive"))
      (node (ref "R20") (pin "2") (pinfunction "2_2") (pintype "passive"))
      (node (ref "R22") (pin "2") (pinfunction "2_2") (pintype "passive"))
      (node (ref "R24") (pin "2") (pinfunction "2_2") (pintype "passive"))
      (node (ref "R26") (pin "2") (pinfunction "2_2") (pintype "passive"))
      (node (ref "R28") (pin "2") (pinfunction "2_2") (pintype "passive"))
      (node (ref "R30") (pin "2") (pinfunction "2_2") (pintype "passive"))
      (node (ref "R32") (pin "2") (pinfunction "2_2") (pintype "passive"))
      (node (ref "R6") (pin "2") (pinfunction "2_2") (pintype "passive"))
      (node (ref "R8") (pin "2") (pinfunction "2_2") (pintype "passive"))
      (node (ref "U16") (pin "1") (pinfunction "OUT_1") (pintype "passive"))
    )
    (net (code "33") (name "/PA0-2") (class "Default")
      (node (ref "JP10") (pin "13") (pinfunction "13_13") (pintype "passive"))
      (node (ref "JP2") (pin "4") (pinfunction "4_4") (pintype "passive"))
    )
    (net (code "34") (name "/PA0-3") (class "Default")
      (node (ref "JP11") (pin "13") (pinfunction "13_13") (pintype "passive"))
      (node (ref "JP15") (pin "4") (pinfunction "4_4") (pintype "passive"))
    )
    (net (code "35") (name "/PA1-2") (class "Default")
      (node (ref "JP10") (pin "14") (pinfunction "14_14") (pintype "passive"))
      (node (ref "JP2") (pin "3") (pinfunction "3_3") (pintype "passive"))
    )
    (net (code "36") (name "/PA1-3") (class "Default")
      (node (ref "JP11") (pin "14") (pinfunction "14_14") (pintype "passive"))
      (node (ref "JP15") (pin "3") (pinfunction "3_3") (pintype "passive"))
    )
    (net (code "37") (name "/PA1_1") (class "Default")
      (node (ref "JP1") (pin "3") (pinfunction "3_3") (pintype "passive"))
      (node (ref "JP9") (pin "14") (pinfunction "14_14") (pintype "passive"))
    )
    (net (code "38") (name "/PA2-2") (class "Default")
      (node (ref "JP10") (pin "15") (pinfunction "15_15") (pintype "passive"))
      (node (ref "JP2") (pin "2") (pinfunction "2_2") (pintype "passive"))
    )
    (net (code "39") (name "/PA2-3") (class "Default")
      (node (ref "JP11") (pin "15") (pinfunction "15_15") (pintype "passive"))
      (node (ref "JP15") (pin "2") (pinfunction "2_2") (pintype "passive"))
    )
    (net (code "40") (name "/PA3-2") (class "Default")
      (node (ref "JP10") (pin "16") (pinfunction "16_16") (pintype "passive"))
      (node (ref "JP2") (pin "1") (pinfunction "1_1") (pintype "passive"))
    )
    (net (code "41") (name "/PA3-3") (class "Default")
      (node (ref "JP11") (pin "16") (pinfunction "16_16") (pintype "passive"))
      (node (ref "JP15") (pin "1") (pinfunction "1_1") (pintype "passive"))
    )
    (net (code "42") (name "/PA3_1") (class "Default")
      (node (ref "JP1") (pin "1") (pinfunction "1_1") (pintype "passive"))
      (node (ref "JP9") (pin "16") (pinfunction "16_16") (pintype "passive"))
    )
    (net (code "43") (name "/SPI1_CS") (class "Default")
      (node (ref "JP10") (pin "17") (pinfunction "17_17") (pintype "passive"))
      (node (ref "JP11") (pin "17") (pinfunction "17_17") (pintype "passive"))
      (node (ref "JP9") (pin "17") (pinfunction "17_17") (pintype "passive"))
      (node (ref "X7") (pin "9") (pinfunction "KL_9") (pintype "passive"))
    )
    (net (code "44") (name "/SPI1_MISO") (class "Default")
      (node (ref "JP10") (pin "19") (pinfunction "19_19") (pintype "passive"))
      (node (ref "JP11") (pin "19") (pinfunction "19_19") (pintype "passive"))
      (node (ref "JP9") (pin "19") (pinfunction "19_19") (pintype "passive"))
      (node (ref "R208") (pin "1") (pinfunction "1_1") (pintype "passive"))
    )
    (net (code "45") (name "/SPI1_MOSI") (class "Default")
      (node (ref "JP10") (pin "20") (pinfunction "20_20") (pintype "passive"))
      (node (ref "JP11") (pin "20") (pinfunction "20_20") (pintype "passive"))
      (node (ref "JP9") (pin "20") (pinfunction "20_20") (pintype "passive"))
      (node (ref "X7") (pin "12") (pinfunction "KL_12") (pintype "passive"))
    )
    (net (code "46") (name "/SPI1_SCK") (class "Default")
      (node (ref "JP10") (pin "18") (pinfunction "18_18") (pintype "passive"))
      (node (ref "JP11") (pin "18") (pinfunction "18_18") (pintype "passive"))
      (node (ref "JP9") (pin "18") (pinfunction "18_18") (pintype "passive"))
      (node (ref "X7") (pin "10") (pinfunction "KL_10") (pintype "passive"))
    )
    (net (code "47") (name "/SPI2_CS") (class "Default")
      (node (ref "JP6") (pin "3") (pinfunction "3_3") (pintype "passive"))
      (node (ref "JP7") (pin "3") (pinfunction "3_3") (pintype "passive"))
      (node (ref "JP8") (pin "3") (pinfunction "3_3") (pintype "passive"))
      (node (ref "X7") (pin "13") (pinfunction "KL_13") (pintype "passive"))
    )
    (net (code "48") (name "/SPI2_MISO") (class "Default")
      (node (ref "JP6") (pin "5") (pinfunction "5_5") (pintype "passive"))
      (node (ref "JP7") (pin "5") (pinfunction "5_5") (pintype "passive"))
      (node (ref "JP8") (pin "5") (pinfunction "5_5") (pintype "passive"))
      (node (ref "R209") (pin "1") (pinfunction "1_1") (pintype "passive"))
    )
    (net (code "49") (name "/SPI2_MOSI") (class "Default")
      (node (ref "JP6") (pin "6") (pinfunction "6_6") (pintype "passive"))
      (node (ref "JP7") (pin "6") (pinfunction "6_6") (pintype "passive"))
      (node (ref "JP8") (pin "6") (pinfunction "6_6") (pintype "passive"))
      (node (ref "X7") (pin "16") (pinfunction "KL_16") (pintype "passive"))
    )
    (net (code "50") (name "/SPI2_SCK") (class "Default")
      (node (ref "JP6") (pin "4") (pinfunction "4_4") (pintype "passive"))
      (node (ref "JP7") (pin "4") (pinfunction "4_4") (pintype "passive"))
      (node (ref "JP8") (pin "4") (pinfunction "4_4") (pintype "passive"))
      (node (ref "X7") (pin "14") (pinfunction "KL_14") (pintype "passive"))
    )
    (net (code "51") (name "/SPI5_CS") (class "Default")
      (node (ref "JP10") (pin "9") (pinfunction "9_9") (pintype "passive"))
      (node (ref "JP11") (pin "9") (pinfunction "9_9") (pintype "passive"))
      (node (ref "JP9") (pin "9") (pinfunction "9_9") (pintype "passive"))
      (node (ref "X7") (pin "5") (pinfunction "KL_5") (pintype "passive"))
    )
    (net (code "52") (name "/SPI5_MISO") (class "Default")
      (node (ref "JP10") (pin "7") (pinfunction "7_7") (pintype "passive"))
      (node (ref "JP11") (pin "7") (pinfunction "7_7") (pintype "passive"))
      (node (ref "JP9") (pin "7") (pinfunction "7_7") (pintype "passive"))
      (node (ref "R112") (pin "1") (pinfunction "1_1") (pintype "passive"))
    )
    (net (code "53") (name "/SPI5_MOSI") (class "Default")
      (node (ref "JP10") (pin "8") (pinfunction "8_8") (pintype "passive"))
      (node (ref "JP11") (pin "8") (pinfunction "8_8") (pintype "passive"))
      (node (ref "JP9") (pin "8") (pinfunction "8_8") (pintype "passive"))
      (node (ref "X7") (pin "8") (pinfunction "KL_8") (pintype "passive"))
    )
    (net (code "54") (name "/SPI5_SCK") (class "Default")
      (node (ref "JP10") (pin "10") (pinfunction "10_10") (pintype "passive"))
      (node (ref "JP11") (pin "10") (pinfunction "10_10") (pintype "passive"))
      (node (ref "JP9") (pin "10") (pinfunction "10_10") (pintype "passive"))
      (node (ref "X7") (pin "6") (pinfunction "KL_6") (pintype "passive"))
    )
    (net (code "55") (name "3V3D3") (class "Default")
      (node (ref "C162") (pin "1") (pinfunction "1_1") (pintype "passive"))
      (node (ref "C164") (pin "1") (pinfunction "1_1") (pintype "passive"))
      (node (ref "J1") (pin "3") (pinfunction "3_3") (pintype "bidirectional"))
      (node (ref "R125") (pin "1") (pinfunction "1_1") (pintype "passive"))
      (node (ref "R134") (pin "2") (pinfunction "2_2") (pintype "passive"))
      (node (ref "U20") (pin "24") (pinfunction "VCC_24") (pintype "power_in"))
    )
    (net (code "56") (name "AGND1") (class "Default")
      (node (ref "U1") (pin "15") (pinfunction "GND_15") (pintype "power_in"))
      (node (ref "VR1") (pin "P$3") (pinfunction "A_P$3") (pintype "passive"))
      (node (ref "VR2") (pin "P$3") (pinfunction "A_P$3") (pintype "passive"))
      (node (ref "VR3") (pin "P$3") (pinfunction "A_P$3") (pintype "passive"))
      (node (ref "VR4") (pin "P$3") (pinfunction "A_P$3") (pintype "passive"))
      (node (ref "VR5") (pin "P$3") (pinfunction "A_P$3") (pintype "passive"))
      (node (ref "VR6") (pin "P$3") (pinfunction "A_P$3") (pintype "passive"))
      (node (ref "VR7") (pin "P$3") (pinfunction "A_P$3") (pintype "passive"))
      (node (ref "VR8") (pin "P$3") (pinfunction "A_P$3") (pintype "passive"))
    )
    (net (code "57") (name "AGND5") (class "Default")
      (node (ref "C47") (pin "2") (pinfunction "2_2") (pintype "passive"))
      (node (ref "C48") (pin "1") (pinfunction "1_1") (pintype "passive"))
      (node (ref "C49") (pin "1") (pinfunction "1_1") (pintype "passive"))
      (node (ref "C50") (pin "2") (pinfunction "2_2") (pintype "passive"))
      (node (ref "C51") (pin "2") (pinfunction "2_2") (pintype "passive"))
      (node (ref "C52") (pin "1") (pinfunction "1_1") (pintype "passive"))
      (node (ref "C53") (pin "2") (pinfunction "2_2") (pintype "passive"))
      (node (ref "C54") (pin "1") (pinfunction "1_1") (pintype "passive"))
      (node (ref "C56") (pin "2") (pinfunction "2_2") (pintype "passive"))
      (node (ref "C57") (pin "1") (pinfunction "1_1") (pintype "passive"))
      (node (ref "C58") (pin "2") (pinfunction "2_2") (pintype "passive"))
      (node (ref "C59") (pin "1") (pinfunction "1_1") (pintype "passive"))
      (node (ref "IC16") (pin "10") (pinfunction "+IN_10") (pintype "input"))
      (node (ref "IC16") (pin "12") (pinfunction "+IN_12") (pintype "input"))
      (node (ref "IC16") (pin "3") (pinfunction "+IN_3") (pintype "input"))
      (node (ref "IC16") (pin "5") (pinfunction "+IN_5") (pintype "input"))
      (node (ref "IC5") (pin "GND") (pinfunction "GND_GND") (pintype "input"))
      (node (ref "IC6") (pin "GND") (pinfunction "GND_GND") (pintype "input"))
      (node (ref "J36") (pin "3") (pinfunction "3_3") (pintype "bidirectional"))
      (node (ref "J36") (pin "4") (pinfunction "4_4") (pintype "bidirectional"))
      (node (ref "JP14") (pin "2") (pinfunction "2_2") (pintype "passive"))
      (node (ref "JP3") (pin "3") (pinfunction "3_3") (pintype "passive"))
      (node (ref "JP3") (pin "4") (pinfunction "4_4") (pintype "passive"))
      (node (ref "JP3") (pin "5") (pinfunction "5_5") (pintype "passive"))
      (node (ref "JP3") (pin "6") (pinfunction "6_6") (pintype "passive"))
      (node (ref "JP4") (pin "3") (pinfunction "3_3") (pintype "passive"))
      (node (ref "JP4") (pin "4") (pinfunction "4_4") (pintype "passive"))
      (node (ref "JP4") (pin "5") (pinfunction "5_5") (pintype "passive"))
      (node (ref "JP4") (pin "6") (pinfunction "6_6") (pintype "passive"))
      (node (ref "JP5") (pin "3") (pinfunction "3_3") (pintype "passive"))
      (node (ref "JP5") (pin "4") (pinfunction "4_4") (pintype "passive"))
      (node (ref "JP5") (pin "5") (pinfunction "5_5") (pintype "passive"))
      (node (ref "JP5") (pin "6") (pinfunction "6_6") (pintype "passive"))
      (node (ref "R11") (pin "1") (pinfunction "1_1") (pintype "passive"))
      (node (ref "R185") (pin "2") (pinfunction "2_2") (pintype "passive"))
      (node (ref "U$3") (pin "P$4") (pinfunction "0_P$4") (pintype "bidirectional"))
    )
    (net (code "58") (name "DGND4") (class "Default")
      (node (ref "C117") (pin "2") (pinfunction "2_2") (pintype "passive"))
      (node (ref "C118") (pin "2") (pinfunction "2_2") (pintype "passive"))
      (node (ref "C119") (pin "2") (pinfunction "2_2") (pintype "passive"))
      (node (ref "C120") (pin "2") (pinfunction "2_2") (pintype "passive"))
      (node (ref "DGND5") (pin "1") (pinfunction "1_1") (pintype "passive"))
      (node (ref "JP10") (pin "24") (pinfunction "24_24") (pintype "passive"))
      (node (ref "JP11") (pin "22") (pinfunction "22_22") (pintype "passive"))
      (node (ref "JP6") (pin "20") (pinfunction "20_20") (pintype "passive"))
      (node (ref "JP7") (pin "20") (pinfunction "20_20") (pintype "passive"))
      (node (ref "JP8") (pin "20") (pinfunction "20_20") (pintype "passive"))
      (node (ref "JP9") (pin "22") (pinfunction "22_22") (pintype "passive"))
      (node (ref "JP9") (pin "24") (pinfunction "24_24") (pintype "passive"))
      (node (ref "R111") (pin "2") (pinfunction "2_2") (pintype "passive"))
      (node (ref "R15") (pin "2") (pinfunction "2_2") (pintype "passive"))
      (node (ref "R185") (pin "1") (pinfunction "1_1") (pintype "passive"))
      (node (ref "U17") (pin "GND") (pinfunction "GND_GND") (pintype "input"))
      (node (ref "X7") (pin "2") (pinfunction "KL_2") (pintype "passive"))
      (node (ref "X7") (pin "4") (pinfunction "KL_4") (pintype "passive"))
    )
    (net (code "59") (name "GND-ISO") (class "Default")
      (node (ref "C162") (pin "2") (pinfunction "2_2") (pintype "passive"))
      (node (ref "C164") (pin "2") (pinfunction "2_2") (pintype "passive"))
      (node (ref "J1") (pin "4") (pinfunction "4_4") (pintype "bidirectional"))
      (node (ref "U20") (pin "1") (pinfunction "A0_1") (pintype "input"))
      (node (ref "U20") (pin "12") (pinfunction "GND_12") (pintype "power_in"))
      (node (ref "U20") (pin "21") (pinfunction "A2_21") (pintype "input"))
    )
    (net (code "60") (name "Net-(3V3A_0A-Pad1)") (class "Default")
      (node (ref "3V3A_0A") (pin "1") (pinfunction "1_1") (pintype "passive"))
      (node (ref "JP10") (pin "12") (pinfunction "12_12") (pintype "passive"))
    )
    (net (code "61") (name "Net-(3V3A_0B-Pad1)") (class "Default")
      (node (ref "3V3A_0B") (pin "1") (pinfunction "1_1") (pintype "passive"))
      (node (ref "JP11") (pin "12") (pinfunction "12_12") (pintype "passive"))
    )
    (net (code "62") (name "Net-(3V3A_0C-Pad1)") (class "Default")
      (node (ref "3V3A_0C") (pin "1") (pinfunction "1_1") (pintype "passive"))
      (node (ref "JP9") (pin "12") (pinfunction "12_12") (pintype "passive"))
    )
    (net (code "63") (name "Net-(C158-Pad-)") (class "Default")
      (node (ref "C158") (pin "-") (pinfunction "-_-") (pintype "passive"))
      (node (ref "R10") (pin "1") (pinfunction "1_1") (pintype "passive"))
    )
    (net (code "64") (name "Net-(IC16A--IN)") (class "Default")
      (node (ref "IC16") (pin "2") (pinfunction "-IN_2") (pintype "input"))
      (node (ref "R159") (pin "1") (pinfunction "1_1") (pintype "passive"))
      (node (ref "R160") (pin "2") (pinfunction "2_2") (pintype "passive"))
      (node (ref "R161") (pin "2") (pinfunction "2_2") (pintype "passive"))
      (node (ref "R162") (pin "2") (pinfunction "2_2") (pintype "passive"))
    )
    (net (code "65") (name "Net-(IC16A-OUT)") (class "Default")
      (node (ref "C158") (pin "+") (pinfunction "+_+") (pintype "passive"))
      (node (ref "IC16") (pin "1") (pinfunction "OUT_1") (pintype "output"))
      (node (ref "R159") (pin "2") (pinfunction "2_2") (pintype "passive"))
    )
    (net (code "66") (name "Net-(IC16B--IN)") (class "Default")
      (node (ref "IC16") (pin "6") (pinfunction "-IN_6") (pintype "input"))
      (node (ref "R167") (pin "2") (pinfunction "2_2") (pintype "passive"))
      (node (ref "R168") (pin "2") (pinfunction "2_2") (pintype "passive"))
      (node (ref "R169") (pin "1") (pinfunction "1_1") (pintype "passive"))
    )
    (net (code "67") (name "Net-(IC16B-OUT)") (class "Default")
      (node (ref "IC16") (pin "7") (pinfunction "OUT_7") (pintype "output"))
      (node (ref "R169") (pin "2") (pinfunction "2_2") (pintype "passive"))
      (node (ref "R9") (pin "1") (pinfunction "1_1") (pintype "passive"))
    )
    (net (code "68") (name "Net-(IC16C--IN)") (class "Default")
      (node (ref "IC16") (pin "9") (pinfunction "-IN_9") (pintype "input"))
      (node (ref "R177") (pin "2") (pinfunction "2_2") (pintype "passive"))
      (node (ref "R178") (pin "2") (pinfunction "2_2") (pintype "passive"))
      (node (ref "R183") (pin "1") (pinfunction "1_1") (pintype "passive"))
    )
    (net (code "69") (name "Net-(IC16C-OUT)") (class "Default")
      (node (ref "IC16") (pin "8") (pinfunction "OUT_8") (pintype "output"))
      (node (ref "R13") (pin "1") (pinfunction "1_1") (pintype "passive"))
      (node (ref "R183") (pin "2") (pinfunction "2_2") (pintype "passive"))
    )
    (net (code "70") (name "Net-(IC16D--IN)") (class "Default")
      (node (ref "IC16") (pin "13") (pinfunction "-IN_13") (pintype "input"))
      (node (ref "R170") (pin "2") (pinfunction "2_2") (pintype "passive"))
      (node (ref "R175") (pin "2") (pinfunction "2_2") (pintype "passive"))
      (node (ref "R176") (pin "1") (pinfunction "1_1") (pintype "passive"))
    )
    (net (code "71") (name "Net-(IC16D-OUT)") (class "Default")
      (node (ref "IC16") (pin "14") (pinfunction "OUT_14") (pintype "output"))
      (node (ref "R176") (pin "2") (pinfunction "2_2") (pintype "passive"))
      (node (ref "R184") (pin "1") (pinfunction "1_1") (pintype "passive"))
    )
    (net (code "72") (name "Net-(J36-Pad1)") (class "Default")
      (node (ref "J36") (pin "1") (pinfunction "1_1") (pintype "bidirectional"))
      (node (ref "J36") (pin "2") (pinfunction "2_2") (pintype "bidirectional"))
      (node (ref "JP14") (pin "1") (pinfunction "1_1") (pintype "passive"))
      (node (ref "R10") (pin "2") (pinfunction "2_2") (pintype "passive"))
      (node (ref "R11") (pin "2") (pinfunction "2_2") (pintype "passive"))
    )
    (net (code "73") (name "Net-(JP1-Pad2)") (class "Default")
      (node (ref "JP1") (pin "2") (pinfunction "2_2") (pintype "passive"))
      (node (ref "JP9") (pin "15") (pinfunction "15_15") (pintype "passive"))
    )
    (net (code "74") (name "Net-(JP1-Pad4)") (class "Default")
      (node (ref "JP1") (pin "4") (pinfunction "4_4") (pintype "passive"))
      (node (ref "JP9") (pin "13") (pinfunction "13_13") (pintype "passive"))
    )
    (net (code "75") (name "Net-(U$3--12VOUT)") (class "Default")
      (node (ref "-15VA") (pin "1") (pinfunction "1_1") (pintype "passive"))
      (node (ref "C49") (pin "2") (pinfunction "2_2") (pintype "passive"))
      (node (ref "C54") (pin "2") (pinfunction "2_2") (pintype "passive"))
      (node (ref "IC6") (pin "IN") (pinfunction "IN_IN") (pintype "input"))
      (node (ref "U$3") (pin "P$3") (pinfunction "-12VOUT_P$3") (pintype "bidirectional"))
    )
    (net (code "76") (name "Net-(U$3-12VOUT)") (class "Default")
      (node (ref "+15VA") (pin "1") (pinfunction "1_1") (pintype "passive"))
      (node (ref "C50") (pin "1") (pinfunction "1_1") (pintype "passive"))
      (node (ref "C53") (pin "1") (pinfunction "1_1") (pintype "passive"))
      (node (ref "IC5") (pin "IN") (pinfunction "IN_IN") (pintype "input"))
      (node (ref "U$3") (pin "P$5") (pinfunction "12VOUT_P$5") (pintype "bidirectional"))
    )
    (net (code "77") (name "Net-(U$3-VIN+)") (class "Default")
      (node (ref "C121") (pin "1") (pinfunction "1_1") (pintype "passive"))
      (node (ref "C122") (pin "1") (pinfunction "1_1") (pintype "passive"))
      (node (ref "R110") (pin "1") (pinfunction "1_1") (pintype "passive"))
      (node (ref "R14") (pin "1") (pinfunction "1_1") (pintype "passive"))
      (node (ref "U$3") (pin "P$1") (pinfunction "VIN+_P$1") (pintype "bidirectional"))
      (node (ref "VREGIN") (pin "1") (pinfunction "1_1") (pintype "passive"))
    )
    (net (code "78") (name "Net-(U$3-VIN-)") (class "Default")
      (node (ref "C121") (pin "2") (pinfunction "2_2") (pintype "passive"))
      (node (ref "C122") (pin "2") (pinfunction "2_2") (pintype "passive"))
      (node (ref "R111") (pin "1") (pinfunction "1_1") (pintype "passive"))
      (node (ref "R15") (pin "1") (pinfunction "1_1") (pintype "passive"))
      (node (ref "U$3") (pin "P$2") (pinfunction "VIN-_P$2") (pintype "bidirectional"))
      (node (ref "VREGGND") (pin "1") (pinfunction "1_1") (pintype "passive"))
    )
    (net (code "79") (name "Net-(U1-AIN0)") (class "Default")
      (node (ref "U1") (pin "5") (pinfunction "AIN0_5") (pintype "input"))
      (node (ref "VR1") (pin "P$2") (pinfunction "S_P$2") (pintype "passive"))
    )
    (net (code "80") (name "Net-(U1-AIN1)") (class "Default")
      (node (ref "U1") (pin "6") (pinfunction "AIN1_6") (pintype "input"))
      (node (ref "VR2") (pin "P$2") (pinfunction "S_P$2") (pintype "passive"))
    )
    (net (code "81") (name "Net-(U1-AIN2)") (class "Default")
      (node (ref "U1") (pin "7") (pinfunction "AIN2_7") (pintype "input"))
      (node (ref "VR3") (pin "P$2") (pinfunction "S_P$2") (pintype "passive"))
    )
    (net (code "82") (name "Net-(U1-AIN3)") (class "Default")
      (node (ref "U1") (pin "8") (pinfunction "AIN3_8") (pintype "input"))
      (node (ref "VR4") (pin "P$2") (pinfunction "S_P$2") (pintype "passive"))
    )
    (net (code "83") (name "Net-(U1-AIN4)") (class "Default")
      (node (ref "U1") (pin "9") (pinfunction "AIN4_9") (pintype "input"))
      (node (ref "VR5") (pin "P$2") (pinfunction "S_P$2") (pintype "passive"))
    )
    (net (code "84") (name "Net-(U1-AIN5)") (class "Default")
      (node (ref "U1") (pin "10") (pinfunction "AIN5_10") (pintype "input"))
      (node (ref "VR6") (pin "P$2") (pinfunction "S_P$2") (pintype "passive"))
    )
    (net (code "85") (name "Net-(U1-AIN6)") (class "Default")
      (node (ref "U1") (pin "11") (pinfunction "AIN6_11") (pintype "input"))
      (node (ref "VR7") (pin "P$2") (pinfunction "S_P$2") (pintype "passive"))
    )
    (net (code "86") (name "Net-(U1-AIN7)") (class "Default")
      (node (ref "U1") (pin "12") (pinfunction "AIN7_12") (pintype "input"))
      (node (ref "VR8") (pin "P$2") (pinfunction "S_P$2") (pintype "passive"))
    )
    (net (code "87") (name "Net-(U1-SCL)") (class "Default")
      (node (ref "J1") (pin "1") (pinfunction "1_1") (pintype "bidirectional"))
      (node (ref "U1") (pin "13") (pinfunction "SCL_13") (pintype "input"))
      (node (ref "U20") (pin "22") (pinfunction "SCL_22") (pintype "input"))
    )
    (net (code "88") (name "Net-(U1-SDA)") (class "Default")
      (node (ref "J1") (pin "2") (pinfunction "2_2") (pintype "bidirectional"))
      (node (ref "U1") (pin "14") (pinfunction "SDA_14") (pintype "bidirectional"))
      (node (ref "U20") (pin "23") (pinfunction "SDA_23") (pintype "bidirectional"))
    )
    (net (code "89") (name "Net-(U3-A)") (class "Default")
      (node (ref "R2") (pin "1") (pinfunction "1_1") (pintype "passive"))
      (node (ref "U3") (pin "1") (pinfunction "A_1") (pintype "bidirectional"))
    )
    (net (code "90") (name "Net-(U4-A)") (class "Default")
      (node (ref "R6") (pin "1") (pinfunction "1_1") (pintype "passive"))
      (node (ref "U4") (pin "1") (pinfunction "A_1") (pintype "bidirectional"))
    )
    (net (code "91") (name "Net-(U5-A)") (class "Default")
      (node (ref "R8") (pin "1") (pinfunction "1_1") (pintype "passive"))
      (node (ref "U5") (pin "1") (pinfunction "A_1") (pintype "bidirectional"))
    )
    (net (code "92") (name "Net-(U6-A)") (class "Default")
      (node (ref "R16") (pin "1") (pinfunction "1_1") (pintype "passive"))
      (node (ref "U6") (pin "1") (pinfunction "A_1") (pintype "bidirectional"))
    )
    (net (code "93") (name "Net-(U7-A)") (class "Default")
      (node (ref "R18") (pin "1") (pinfunction "1_1") (pintype "passive"))
      (node (ref "U7") (pin "1") (pinfunction "A_1") (pintype "bidirectional"))
    )
    (net (code "94") (name "Net-(U8-A)") (class "Default")
      (node (ref "R20") (pin "1") (pinfunction "1_1") (pintype "passive"))
      (node (ref "U8") (pin "1") (pinfunction "A_1") (pintype "bidirectional"))
    )
    (net (code "95") (name "Net-(U9-A)") (class "Default")
      (node (ref "R22") (pin "1") (pinfunction "1_1") (pintype "passive"))
      (node (ref "U9") (pin "1") (pinfunction "A_1") (pintype "bidirectional"))
    )
    (net (code "96") (name "Net-(U10-A)") (class "Default")
      (node (ref "R26") (pin "1") (pinfunction "1_1") (pintype "passive"))
      (node (ref "U10") (pin "1") (pinfunction "A_1") (pintype "bidirectional"))
    )
    (net (code "97") (name "Net-(U11-A)") (class "Default")
      (node (ref "R28") (pin "1") (pinfunction "1_1") (pintype "passive"))
      (node (ref "U11") (pin "1") (pinfunction "A_1") (pintype "bidirectional"))
    )
    (net (code "98") (name "Net-(U12-A)") (class "Default")
      (node (ref "R30") (pin "1") (pinfunction "1_1") (pintype "passive"))
      (node (ref "U12") (pin "1") (pinfunction "A_1") (pintype "bidirectional"))
    )
    (net (code "99") (name "Net-(U13-A)") (class "Default")
      (node (ref "R32") (pin "1") (pinfunction "1_1") (pintype "passive"))
      (node (ref "U13") (pin "1") (pinfunction "A_1") (pintype "bidirectional"))
    )
    (net (code "100") (name "Net-(U14-A)") (class "Default")
      (node (ref "R24") (pin "1") (pinfunction "1_1") (pintype "passive"))
      (node (ref "U14") (pin "1") (pinfunction "A_1") (pintype "bidirectional"))
    )
    (net (code "101") (name "Net-(U20-A1)") (class "Default")
      (node (ref "R125") (pin "2") (pinfunction "2_2") (pintype "passive"))
      (node (ref "U20") (pin "2") (pinfunction "A1_2") (pintype "input"))
    )
    (net (code "102") (name "Net-(U20-~{RESET})") (class "Default")
      (node (ref "R134") (pin "1") (pinfunction "1_1") (pintype "passive"))
      (node (ref "U20") (pin "3") (pinfunction "~{RESET}_3") (pintype "input"))
    )
    (net (code "103") (name "Net-(X7C-KL)") (class "Default")
      (node (ref "R208") (pin "2") (pinfunction "2_2") (pintype "passive"))
      (node (ref "X7") (pin "11") (pinfunction "KL_11") (pintype "passive"))
    )
    (net (code "104") (name "Net-(X7G-KL)") (class "Default")
      (node (ref "R209") (pin "2") (pinfunction "2_2") (pintype "passive"))
      (node (ref "X7") (pin "15") (pinfunction "KL_15") (pintype "passive"))
    )
    (net (code "105") (name "Net-(X7N-KL)") (class "Default")
      (node (ref "R112") (pin "2") (pinfunction "2_2") (pintype "passive"))
      (node (ref "X7") (pin "7") (pinfunction "KL_7") (pintype "passive"))
    )
    (net (code "106") (name "SUPPLY0_CGND_") (class "Default")
      (node (ref "C123") (pin "2") (pinfunction "2_2") (pintype "passive"))
      (node (ref "C15") (pin "2") (pinfunction "2_2") (pintype "passive"))
      (node (ref "C16") (pin "2") (pinfunction "2_2") (pintype "passive"))
      (node (ref "C182") (pin "2") (pinfunction "2_2") (pintype "passive"))
      (node (ref "C21") (pin "2") (pinfunction "2_2") (pintype "passive"))
      (node (ref "C22") (pin "2") (pinfunction "2_2") (pintype "passive"))
      (node (ref "DGND4") (pin "1") (pinfunction "1_1") (pintype "passive"))
      (node (ref "U10") (pin "2") (pinfunction "K_2") (pintype "bidirectional"))
      (node (ref "U10") (pin "4") (pinfunction "E_4") (pintype "bidirectional"))
      (node (ref "U11") (pin "2") (pinfunction "K_2") (pintype "bidirectional"))
      (node (ref "U11") (pin "4") (pinfunction "E_4") (pintype "bidirectional"))
      (node (ref "U12") (pin "2") (pinfunction "K_2") (pintype "bidirectional"))
      (node (ref "U12") (pin "4") (pinfunction "E_4") (pintype "bidirectional"))
      (node (ref "U13") (pin "2") (pinfunction "K_2") (pintype "bidirectional"))
      (node (ref "U13") (pin "4") (pinfunction "E_4") (pintype "bidirectional"))
      (node (ref "U14") (pin "2") (pinfunction "K_2") (pintype "bidirectional"))
      (node (ref "U14") (pin "4") (pinfunction "E_4") (pintype "bidirectional"))
      (node (ref "U16") (pin "2") (pinfunction "GND_2") (pintype "power_in"))
      (node (ref "U3") (pin "2") (pinfunction "K_2") (pintype "bidirectional"))
      (node (ref "U3") (pin "4") (pinfunction "E_4") (pintype "bidirectional"))
      (node (ref "U4") (pin "2") (pinfunction "K_2") (pintype "bidirectional"))
      (node (ref "U4") (pin "4") (pinfunction "E_4") (pintype "bidirectional"))
      (node (ref "U5") (pin "2") (pinfunction "K_2") (pintype "bidirectional"))
      (node (ref "U5") (pin "4") (pinfunction "E_4") (pintype "bidirectional"))
      (node (ref "U6") (pin "2") (pinfunction "K_2") (pintype "bidirectional"))
      (node (ref "U6") (pin "4") (pinfunction "E_4") (pintype "bidirectional"))
      (node (ref "U7") (pin "2") (pinfunction "K_2") (pintype "bidirectional"))
      (node (ref "U7") (pin "4") (pinfunction "E_4") (pintype "bidirectional"))
      (node (ref "U8") (pin "2") (pinfunction "K_2") (pintype "bidirectional"))
      (node (ref "U8") (pin "4") (pinfunction "E_4") (pintype "bidirectional"))
      (node (ref "U9") (pin "2") (pinfunction "K_2") (pintype "bidirectional"))
      (node (ref "U9") (pin "4") (pinfunction "E_4") (pintype "bidirectional"))
      (node (ref "X10") (pin "13") (pinfunction "KL_13") (pintype "passive"))
      (node (ref "X10") (pin "15") (pinfunction "KL_15") (pintype "passive"))
    )
    (net (code "107") (name "unconnected-(JP6-Pad1)") (class "Default")
      (node (ref "JP6") (pin "1") (pinfunction "1_1") (pintype "passive"))
    )
    (net (code "108") (name "unconnected-(JP6-Pad2)") (class "Default")
      (node (ref "JP6") (pin "2") (pinfunction "2_2") (pintype "passive"))
    )
    (net (code "109") (name "unconnected-(JP6-Pad7)") (class "Default")
      (node (ref "JP6") (pin "7") (pinfunction "7_7") (pintype "passive"))
    )
    (net (code "110") (name "unconnected-(JP6-Pad8)") (class "Default")
      (node (ref "JP6") (pin "8") (pinfunction "8_8") (pintype "passive"))
    )
    (net (code "111") (name "unconnected-(JP6-Pad9)") (class "Default")
      (node (ref "JP6") (pin "9") (pinfunction "9_9") (pintype "passive"))
    )
    (net (code "112") (name "unconnected-(JP6-Pad10)") (class "Default")
      (node (ref "JP6") (pin "10") (pinfunction "10_10") (pintype "passive"))
    )
    (net (code "113") (name "unconnected-(JP6-Pad11)") (class "Default")
      (node (ref "JP6") (pin "11") (pinfunction "11_11") (pintype "passive"))
    )
    (net (code "114") (name "unconnected-(JP6-Pad12)") (class "Default")
      (node (ref "JP6") (pin "12") (pinfunction "12_12") (pintype "passive"))
    )
    (net (code "115") (name "unconnected-(JP6-Pad13)") (class "Default")
      (node (ref "JP6") (pin "13") (pinfunction "13_13") (pintype "passive"))
    )
    (net (code "116") (name "unconnected-(JP6-Pad14)") (class "Default")
      (node (ref "JP6") (pin "14") (pinfunction "14_14") (pintype "passive"))
    )
    (net (code "117") (name "unconnected-(JP6-Pad15)") (class "Default")
      (node (ref "JP6") (pin "15") (pinfunction "15_15") (pintype "passive"))
    )
    (net (code "118") (name "unconnected-(JP6-Pad16)") (class "Default")
      (node (ref "JP6") (pin "16") (pinfunction "16_16") (pintype "passive"))
    )
    (net (code "119") (name "unconnected-(JP6-Pad17)") (class "Default")
      (node (ref "JP6") (pin "17") (pinfunction "17_17") (pintype "passive"))
    )
    (net (code "120") (name "unconnected-(JP6-Pad18)") (class "Default")
      (node (ref "JP6") (pin "18") (pinfunction "18_18") (pintype "passive"))
    )
    (net (code "121") (name "unconnected-(JP7-Pad1)") (class "Default")
      (node (ref "JP7") (pin "1") (pinfunction "1_1") (pintype "passive"))
    )
    (net (code "122") (name "unconnected-(JP7-Pad2)") (class "Default")
      (node (ref "JP7") (pin "2") (pinfunction "2_2") (pintype "passive"))
    )
    (net (code "123") (name "unconnected-(JP7-Pad7)") (class "Default")
      (node (ref "JP7") (pin "7") (pinfunction "7_7") (pintype "passive"))
    )
    (net (code "124") (name "unconnected-(JP7-Pad8)") (class "Default")
      (node (ref "JP7") (pin "8") (pinfunction "8_8") (pintype "passive"))
    )
    (net (code "125") (name "unconnected-(JP7-Pad9)") (class "Default")
      (node (ref "JP7") (pin "9") (pinfunction "9_9") (pintype "passive"))
    )
    (net (code "126") (name "unconnected-(JP7-Pad10)") (class "Default")
      (node (ref "JP7") (pin "10") (pinfunction "10_10") (pintype "passive"))
    )
    (net (code "127") (name "unconnected-(JP7-Pad11)") (class "Default")
      (node (ref "JP7") (pin "11") (pinfunction "11_11") (pintype "passive"))
    )
    (net (code "128") (name "unconnected-(JP7-Pad12)") (class "Default")
      (node (ref "JP7") (pin "12") (pinfunction "12_12") (pintype "passive"))
    )
    (net (code "129") (name "unconnected-(JP7-Pad13)") (class "Default")
      (node (ref "JP7") (pin "13") (pinfunction "13_13") (pintype "passive"))
    )
    (net (code "130") (name "unconnected-(JP7-Pad14)") (class "Default")
      (node (ref "JP7") (pin "14") (pinfunction "14_14") (pintype "passive"))
    )
    (net (code "131") (name "unconnected-(JP7-Pad15)") (class "Default")
      (node (ref "JP7") (pin "15") (pinfunction "15_15") (pintype "passive"))
    )
    (net (code "132") (name "unconnected-(JP7-Pad16)") (class "Default")
      (node (ref "JP7") (pin "16") (pinfunction "16_16") (pintype "passive"))
    )
    (net (code "133") (name "unconnected-(JP7-Pad17)") (class "Default")
      (node (ref "JP7") (pin "17") (pinfunction "17_17") (pintype "passive"))
    )
    (net (code "134") (name "unconnected-(JP7-Pad18)") (class "Default")
      (node (ref "JP7") (pin "18") (pinfunction "18_18") (pintype "passive"))
    )
    (net (code "135") (name "unconnected-(JP8-Pad1)") (class "Default")
      (node (ref "JP8") (pin "1") (pinfunction "1_1") (pintype "passive"))
    )
    (net (code "136") (name "unconnected-(JP8-Pad2)") (class "Default")
      (node (ref "JP8") (pin "2") (pinfunction "2_2") (pintype "passive"))
    )
    (net (code "137") (name "unconnected-(JP8-Pad7)") (class "Default")
      (node (ref "JP8") (pin "7") (pinfunction "7_7") (pintype "passive"))
    )
    (net (code "138") (name "unconnected-(JP8-Pad8)") (class "Default")
      (node (ref "JP8") (pin "8") (pinfunction "8_8") (pintype "passive"))
    )
    (net (code "139") (name "unconnected-(JP8-Pad9)") (class "Default")
      (node (ref "JP8") (pin "9") (pinfunction "9_9") (pintype "passive"))
    )
    (net (code "140") (name "unconnected-(JP8-Pad10)") (class "Default")
      (node (ref "JP8") (pin "10") (pinfunction "10_10") (pintype "passive"))
    )
    (net (code "141") (name "unconnected-(JP8-Pad11)") (class "Default")
      (node (ref "JP8") (pin "11") (pinfunction "11_11") (pintype "passive"))
    )
    (net (code "142") (name "unconnected-(JP8-Pad12)") (class "Default")
      (node (ref "JP8") (pin "12") (pinfunction "12_12") (pintype "passive"))
    )
    (net (code "143") (name "unconnected-(JP8-Pad13)") (class "Default")
      (node (ref "JP8") (pin "13") (pinfunction "13_13") (pintype "passive"))
    )
    (net (code "144") (name "unconnected-(JP8-Pad14)") (class "Default")
      (node (ref "JP8") (pin "14") (pinfunction "14_14") (pintype "passive"))
    )
    (net (code "145") (name "unconnected-(JP8-Pad15)") (class "Default")
      (node (ref "JP8") (pin "15") (pinfunction "15_15") (pintype "passive"))
    )
    (net (code "146") (name "unconnected-(JP8-Pad16)") (class "Default")
      (node (ref "JP8") (pin "16") (pinfunction "16_16") (pintype "passive"))
    )
    (net (code "147") (name "unconnected-(JP8-Pad17)") (class "Default")
      (node (ref "JP8") (pin "17") (pinfunction "17_17") (pintype "passive"))
    )
    (net (code "148") (name "unconnected-(JP8-Pad18)") (class "Default")
      (node (ref "JP8") (pin "18") (pinfunction "18_18") (pintype "passive"))
    )
    (net (code "149") (name "unconnected-(JP9-Pad1)") (class "Default")
      (node (ref "JP9") (pin "1") (pinfunction "1_1") (pintype "passive"))
    )
    (net (code "150") (name "unconnected-(JP9-Pad2)") (class "Default")
      (node (ref "JP9") (pin "2") (pinfunction "2_2") (pintype "passive"))
    )
    (net (code "151") (name "unconnected-(JP9-Pad3)") (class "Default")
      (node (ref "JP9") (pin "3") (pinfunction "3_3") (pintype "passive"))
    )
    (net (code "152") (name "unconnected-(JP9-Pad4)") (class "Default")
      (node (ref "JP9") (pin "4") (pinfunction "4_4") (pintype "passive"))
    )
    (net (code "153") (name "unconnected-(JP9-Pad5)") (class "Default")
      (node (ref "JP9") (pin "5") (pinfunction "5_5") (pintype "passive"))
    )
    (net (code "154") (name "unconnected-(JP9-Pad6)") (class "Default")
      (node (ref "JP9") (pin "6") (pinfunction "6_6") (pintype "passive"))
    )
    (net (code "155") (name "unconnected-(JP9-Pad11)") (class "Default")
      (node (ref "JP9") (pin "11") (pinfunction "11_11") (pintype "passive"))
    )
    (net (code "156") (name "unconnected-(JP9-Pad21)") (class "Default")
      (node (ref "JP9") (pin "21") (pinfunction "21_21") (pintype "passive"))
    )
    (net (code "157") (name "unconnected-(JP9-Pad23)") (class "Default")
      (node (ref "JP9") (pin "23") (pinfunction "23_23") (pintype "passive"))
    )
    (net (code "158") (name "unconnected-(JP9-Pad25)") (class "Default")
      (node (ref "JP9") (pin "25") (pinfunction "25_25") (pintype "passive"))
    )
    (net (code "159") (name "unconnected-(JP9-Pad26)") (class "Default")
      (node (ref "JP9") (pin "26") (pinfunction "26_26") (pintype "passive"))
    )
    (net (code "160") (name "unconnected-(JP9-Pad27)") (class "Default")
      (node (ref "JP9") (pin "27") (pinfunction "27_27") (pintype "passive"))
    )
    (net (code "161") (name "unconnected-(JP9-Pad28)") (class "Default")
      (node (ref "JP9") (pin "28") (pinfunction "28_28") (pintype "passive"))
    )
    (net (code "162") (name "unconnected-(JP9-Pad29)") (class "Default")
      (node (ref "JP9") (pin "29") (pinfunction "29_29") (pintype "passive"))
    )
    (net (code "163") (name "unconnected-(JP9-Pad30)") (class "Default")
      (node (ref "JP9") (pin "30") (pinfunction "30_30") (pintype "passive"))
    )
    (net (code "164") (name "unconnected-(JP10-Pad1)") (class "Default")
      (node (ref "JP10") (pin "1") (pinfunction "1_1") (pintype "passive"))
    )
    (net (code "165") (name "unconnected-(JP10-Pad2)") (class "Default")
      (node (ref "JP10") (pin "2") (pinfunction "2_2") (pintype "passive"))
    )
    (net (code "166") (name "unconnected-(JP10-Pad3)") (class "Default")
      (node (ref "JP10") (pin "3") (pinfunction "3_3") (pintype "passive"))
    )
    (net (code "167") (name "unconnected-(JP10-Pad4)") (class "Default")
      (node (ref "JP10") (pin "4") (pinfunction "4_4") (pintype "passive"))
    )
    (net (code "168") (name "unconnected-(JP10-Pad5)") (class "Default")
      (node (ref "JP10") (pin "5") (pinfunction "5_5") (pintype "passive"))
    )
    (net (code "169") (name "unconnected-(JP10-Pad6)") (class "Default")
      (node (ref "JP10") (pin "6") (pinfunction "6_6") (pintype "passive"))
    )
    (net (code "170") (name "unconnected-(JP10-Pad11)") (class "Default")
      (node (ref "JP10") (pin "11") (pinfunction "11_11") (pintype "passive"))
    )
    (net (code "171") (name "unconnected-(JP10-Pad21)") (class "Default")
      (node (ref "JP10") (pin "21") (pinfunction "21_21") (pintype "passive"))
    )
    (net (code "172") (name "unconnected-(JP10-Pad22)") (class "Default")
      (node (ref "JP10") (pin "22") (pinfunction "22_22") (pintype "passive"))
    )
    (net (code "173") (name "unconnected-(JP10-Pad23)") (class "Default")
      (node (ref "JP10") (pin "23") (pinfunction "23_23") (pintype "passive"))
    )
    (net (code "174") (name "unconnected-(JP10-Pad25)") (class "Default")
      (node (ref "JP10") (pin "25") (pinfunction "25_25") (pintype "passive"))
    )
    (net (code "175") (name "unconnected-(JP10-Pad26)") (class "Default")
      (node (ref "JP10") (pin "26") (pinfunction "26_26") (pintype "passive"))
    )
    (net (code "176") (name "unconnected-(JP10-Pad27)") (class "Default")
      (node (ref "JP10") (pin "27") (pinfunction "27_27") (pintype "passive"))
    )
    (net (code "177") (name "unconnected-(JP10-Pad28)") (class "Default")
      (node (ref "JP10") (pin "28") (pinfunction "28_28") (pintype "passive"))
    )
    (net (code "178") (name "unconnected-(JP10-Pad29)") (class "Default")
      (node (ref "JP10") (pin "29") (pinfunction "29_29") (pintype "passive"))
    )
    (net (code "179") (name "unconnected-(JP10-Pad30)") (class "Default")
      (node (ref "JP10") (pin "30") (pinfunction "30_30") (pintype "passive"))
    )
    (net (code "180") (name "unconnected-(JP11-Pad1)") (class "Default")
      (node (ref "JP11") (pin "1") (pinfunction "1_1") (pintype "passive"))
    )
    (net (code "181") (name "unconnected-(JP11-Pad2)") (class "Default")
      (node (ref "JP11") (pin "2") (pinfunction "2_2") (pintype "passive"))
    )
    (net (code "182") (name "unconnected-(JP11-Pad3)") (class "Default")
      (node (ref "JP11") (pin "3") (pinfunction "3_3") (pintype "passive"))
    )
    (net (code "183") (name "unconnected-(JP11-Pad4)") (class "Default")
      (node (ref "JP11") (pin "4") (pinfunction "4_4") (pintype "passive"))
    )
    (net (code "184") (name "unconnected-(JP11-Pad5)") (class "Default")
      (node (ref "JP11") (pin "5") (pinfunction "5_5") (pintype "passive"))
    )
    (net (code "185") (name "unconnected-(JP11-Pad6)") (class "Default")
      (node (ref "JP11") (pin "6") (pinfunction "6_6") (pintype "passive"))
    )
    (net (code "186") (name "unconnected-(JP11-Pad11)") (class "Default")
      (node (ref "JP11") (pin "11") (pinfunction "11_11") (pintype "passive"))
    )
    (net (code "187") (name "unconnected-(JP11-Pad21)") (class "Default")
      (node (ref "JP11") (pin "21") (pinfunction "21_21") (pintype "passive"))
    )
    (net (code "188") (name "unconnected-(JP11-Pad23)") (class "Default")
      (node (ref "JP11") (pin "23") (pinfunction "23_23") (pintype "passive"))
    )
    (net (code "189") (name "unconnected-(JP11-Pad24)") (class "Default")
      (node (ref "JP11") (pin "24") (pinfunction "24_24") (pintype "passive"))
    )
    (net (code "190") (name "unconnected-(JP11-Pad25)") (class "Default")
      (node (ref "JP11") (pin "25") (pinfunction "25_25") (pintype "passive"))
    )
    (net (code "191") (name "unconnected-(JP11-Pad26)") (class "Default")
      (node (ref "JP11") (pin "26") (pinfunction "26_26") (pintype "passive"))
    )
    (net (code "192") (name "unconnected-(JP11-Pad27)") (class "Default")
      (node (ref "JP11") (pin "27") (pinfunction "27_27") (pintype "passive"))
    )
    (net (code "193") (name "unconnected-(JP11-Pad28)") (class "Default")
      (node (ref "JP11") (pin "28") (pinfunction "28_28") (pintype "passive"))
    )
    (net (code "194") (name "unconnected-(JP11-Pad29)") (class "Default")
      (node (ref "JP11") (pin "29") (pinfunction "29_29") (pintype "passive"))
    )
    (net (code "195") (name "unconnected-(JP11-Pad30)") (class "Default")
      (node (ref "JP11") (pin "30") (pinfunction "30_30") (pintype "passive"))
    )
    (net (code "196") (name "unconnected-(JP12-Pad1)") (class "Default")
      (node (ref "JP12") (pin "1") (pinfunction "1_1") (pintype "passive"))
    )
    (net (code "197") (name "unconnected-(JP12-Pad2)") (class "Default")
      (node (ref "JP12") (pin "2") (pinfunction "2_2") (pintype "passive"))
    )
    (net (code "198") (name "unconnected-(JP12-Pad3)") (class "Default")
      (node (ref "JP12") (pin "3") (pinfunction "3_3") (pintype "passive"))
    )
    (net (code "199") (name "unconnected-(JP12-Pad4)") (class "Default")
      (node (ref "JP12") (pin "4") (pinfunction "4_4") (pintype "passive"))
    )
    (net (code "200") (name "unconnected-(JP13-Pad1)") (class "Default")
      (node (ref "JP13") (pin "1") (pinfunction "1_1") (pintype "passive"))
    )
    (net (code "201") (name "unconnected-(JP13-Pad2)") (class "Default")
      (node (ref "JP13") (pin "2") (pinfunction "2_2") (pintype "passive"))
    )
    (net (code "202") (name "unconnected-(JP13-Pad3)") (class "Default")
      (node (ref "JP13") (pin "3") (pinfunction "3_3") (pintype "passive"))
    )
    (net (code "203") (name "unconnected-(JP13-Pad4)") (class "Default")
      (node (ref "JP13") (pin "4") (pinfunction "4_4") (pintype "passive"))
    )
    (net (code "204") (name "unconnected-(JP16-Pad1)") (class "Default")
      (node (ref "JP16") (pin "1") (pinfunction "1_1") (pintype "passive"))
    )
    (net (code "205") (name "unconnected-(JP16-Pad2)") (class "Default")
      (node (ref "JP16") (pin "2") (pinfunction "2_2") (pintype "passive"))
    )
    (net (code "206") (name "unconnected-(JP16-Pad3)") (class "Default")
      (node (ref "JP16") (pin "3") (pinfunction "3_3") (pintype "passive"))
    )
    (net (code "207") (name "unconnected-(JP16-Pad4)") (class "Default")
      (node (ref "JP16") (pin "4") (pinfunction "4_4") (pintype "passive"))
    )
    (net (code "208") (name "unconnected-(JP17-Pad1)") (class "Default")
      (node (ref "JP17") (pin "1") (pinfunction "1_1") (pintype "passive"))
    )
    (net (code "209") (name "unconnected-(JP17-Pad2)") (class "Default")
      (node (ref "JP17") (pin "2") (pinfunction "2_2") (pintype "passive"))
    )
    (net (code "210") (name "unconnected-(JP17-Pad3)") (class "Default")
      (node (ref "JP17") (pin "3") (pinfunction "3_3") (pintype "passive"))
    )
    (net (code "211") (name "unconnected-(JP17-Pad4)") (class "Default")
      (node (ref "JP17") (pin "4") (pinfunction "4_4") (pintype "passive"))
    )
    (net (code "212") (name "unconnected-(JP18-Pad1)") (class "Default")
      (node (ref "JP18") (pin "1") (pinfunction "1_1") (pintype "passive"))
    )
    (net (code "213") (name "unconnected-(JP18-Pad2)") (class "Default")
      (node (ref "JP18") (pin "2") (pinfunction "2_2") (pintype "passive"))
    )
    (net (code "214") (name "unconnected-(JP18-Pad3)") (class "Default")
      (node (ref "JP18") (pin "3") (pinfunction "3_3") (pintype "passive"))
    )
    (net (code "215") (name "unconnected-(JP18-Pad4)") (class "Default")
      (node (ref "JP18") (pin "4") (pinfunction "4_4") (pintype "passive"))
    )
    (net (code "216") (name "unconnected-(JP19-Pad1)") (class "Default")
      (node (ref "JP19") (pin "1") (pinfunction "1_1") (pintype "passive"))
    )
    (net (code "217") (name "unconnected-(JP19-Pad2)") (class "Default")
      (node (ref "JP19") (pin "2") (pinfunction "2_2") (pintype "passive"))
    )
    (net (code "218") (name "unconnected-(JP19-Pad3)") (class "Default")
      (node (ref "JP19") (pin "3") (pinfunction "3_3") (pintype "passive"))
    )
    (net (code "219") (name "unconnected-(JP19-Pad4)") (class "Default")
      (node (ref "JP19") (pin "4") (pinfunction "4_4") (pintype "passive"))
    )
    (net (code "220") (name "unconnected-(JP20-Pad1)") (class "Default")
      (node (ref "JP20") (pin "1") (pinfunction "1_1") (pintype "passive"))
    )
    (net (code "221") (name "unconnected-(JP20-Pad2)") (class "Default")
      (node (ref "JP20") (pin "2") (pinfunction "2_2") (pintype "passive"))
    )
    (net (code "222") (name "unconnected-(JP20-Pad3)") (class "Default")
      (node (ref "JP20") (pin "3") (pinfunction "3_3") (pintype "passive"))
    )
    (net (code "223") (name "unconnected-(JP20-Pad4)") (class "Default")
      (node (ref "JP20") (pin "4") (pinfunction "4_4") (pintype "passive"))
    )
    (net (code "224") (name "unconnected-(JP21-Pad1)") (class "Default")
      (node (ref "JP21") (pin "1") (pinfunction "1_1") (pintype "passive"))
    )
    (net (code "225") (name "unconnected-(JP21-Pad2)") (class "Default")
      (node (ref "JP21") (pin "2") (pinfunction "2_2") (pintype "passive"))
    )
    (net (code "226") (name "unconnected-(JP21-Pad3)") (class "Default")
      (node (ref "JP21") (pin "3") (pinfunction "3_3") (pintype "passive"))
    )
    (net (code "227") (name "unconnected-(JP21-Pad4)") (class "Default")
      (node (ref "JP21") (pin "4") (pinfunction "4_4") (pintype "passive"))
    )
    (net (code "228") (name "unconnected-(U1-NC-Pad4)") (class "Default")
      (node (ref "U1") (pin "4") (pinfunction "NC_4") (pintype "no_connect"))
    )
    (net (code "229") (name "unconnected-(U1-NC_2-Pad2)") (class "Default")
      (node (ref "U1") (pin "2") (pinfunction "NC_2_2") (pintype "no_connect"))
    )
    (net (code "230") (name "unconnected-(U1-NC_3-Pad3)") (class "Default")
      (node (ref "U1") (pin "3") (pinfunction "NC_3_3") (pintype "no_connect"))
    )
    (net (code "231") (name "unconnected-(U1-REF-Pad1)") (class "Default")
      (node (ref "U1") (pin "1") (pinfunction "REF_1") (pintype "bidirectional"))
    )
    (net (code "232") (name "unconnected-(U16-~{OC}-Pad3)") (class "Default")
      (node (ref "U16") (pin "3") (pinfunction "~{OC}_3") (pintype "output"))
    )
    (net (code "233") (name "unconnected-(U20-SC0-Pad5)") (class "Default")
      (node (ref "U20") (pin "5") (pinfunction "SC0_5") (pintype "bidirectional"))
    )
    (net (code "234") (name "unconnected-(U20-SC1-Pad7)") (class "Default")
      (node (ref "U20") (pin "7") (pinfunction "SC1_7") (pintype "bidirectional"))
    )
    (net (code "235") (name "unconnected-(U20-SC2-Pad9)") (class "Default")
      (node (ref "U20") (pin "9") (pinfunction "SC2_9") (pintype "bidirectional"))
    )
    (net (code "236") (name "unconnected-(U20-SC3-Pad11)") (class "Default")
      (node (ref "U20") (pin "11") (pinfunction "SC3_11") (pintype "bidirectional"))
    )
    (net (code "237") (name "unconnected-(U20-SC4-Pad14)") (class "Default")
      (node (ref "U20") (pin "14") (pinfunction "SC4_14") (pintype "bidirectional"))
    )
    (net (code "238") (name "unconnected-(U20-SC5-Pad16)") (class "Default")
      (node (ref "U20") (pin "16") (pinfunction "SC5_16") (pintype "bidirectional"))
    )
    (net (code "239") (name "unconnected-(U20-SC6-Pad18)") (class "Default")
      (node (ref "U20") (pin "18") (pinfunction "SC6_18") (pintype "bidirectional"))
    )
    (net (code "240") (name "unconnected-(U20-SC7-Pad20)") (class "Default")
      (node (ref "U20") (pin "20") (pinfunction "SC7_20") (pintype "bidirectional"))
    )
    (net (code "241") (name "unconnected-(U20-SD0-Pad4)") (class "Default")
      (node (ref "U20") (pin "4") (pinfunction "SD0_4") (pintype "bidirectional"))
    )
    (net (code "242") (name "unconnected-(U20-SD1-Pad6)") (class "Default")
      (node (ref "U20") (pin "6") (pinfunction "SD1_6") (pintype "bidirectional"))
    )
    (net (code "243") (name "unconnected-(U20-SD2-Pad8)") (class "Default")
      (node (ref "U20") (pin "8") (pinfunction "SD2_8") (pintype "bidirectional"))
    )
    (net (code "244") (name "unconnected-(U20-SD3-Pad10)") (class "Default")
      (node (ref "U20") (pin "10") (pinfunction "SD3_10") (pintype "bidirectional"))
    )
    (net (code "245") (name "unconnected-(U20-SD4-Pad13)") (class "Default")
      (node (ref "U20") (pin "13") (pinfunction "SD4_13") (pintype "bidirectional"))
    )
    (net (code "246") (name "unconnected-(U20-SD5-Pad15)") (class "Default")
      (node (ref "U20") (pin "15") (pinfunction "SD5_15") (pintype "bidirectional"))
    )
    (net (code "247") (name "unconnected-(U20-SD6-Pad17)") (class "Default")
      (node (ref "U20") (pin "17") (pinfunction "SD6_17") (pintype "bidirectional"))
    )
    (net (code "248") (name "unconnected-(U20-SD7-Pad19)") (class "Default")
      (node (ref "U20") (pin "19") (pinfunction "SD7_19") (pintype "bidirectional"))
    )
  )
)
